# baseboard_0_2.net
KiCad netlist of a schematic drawn in EAGLE
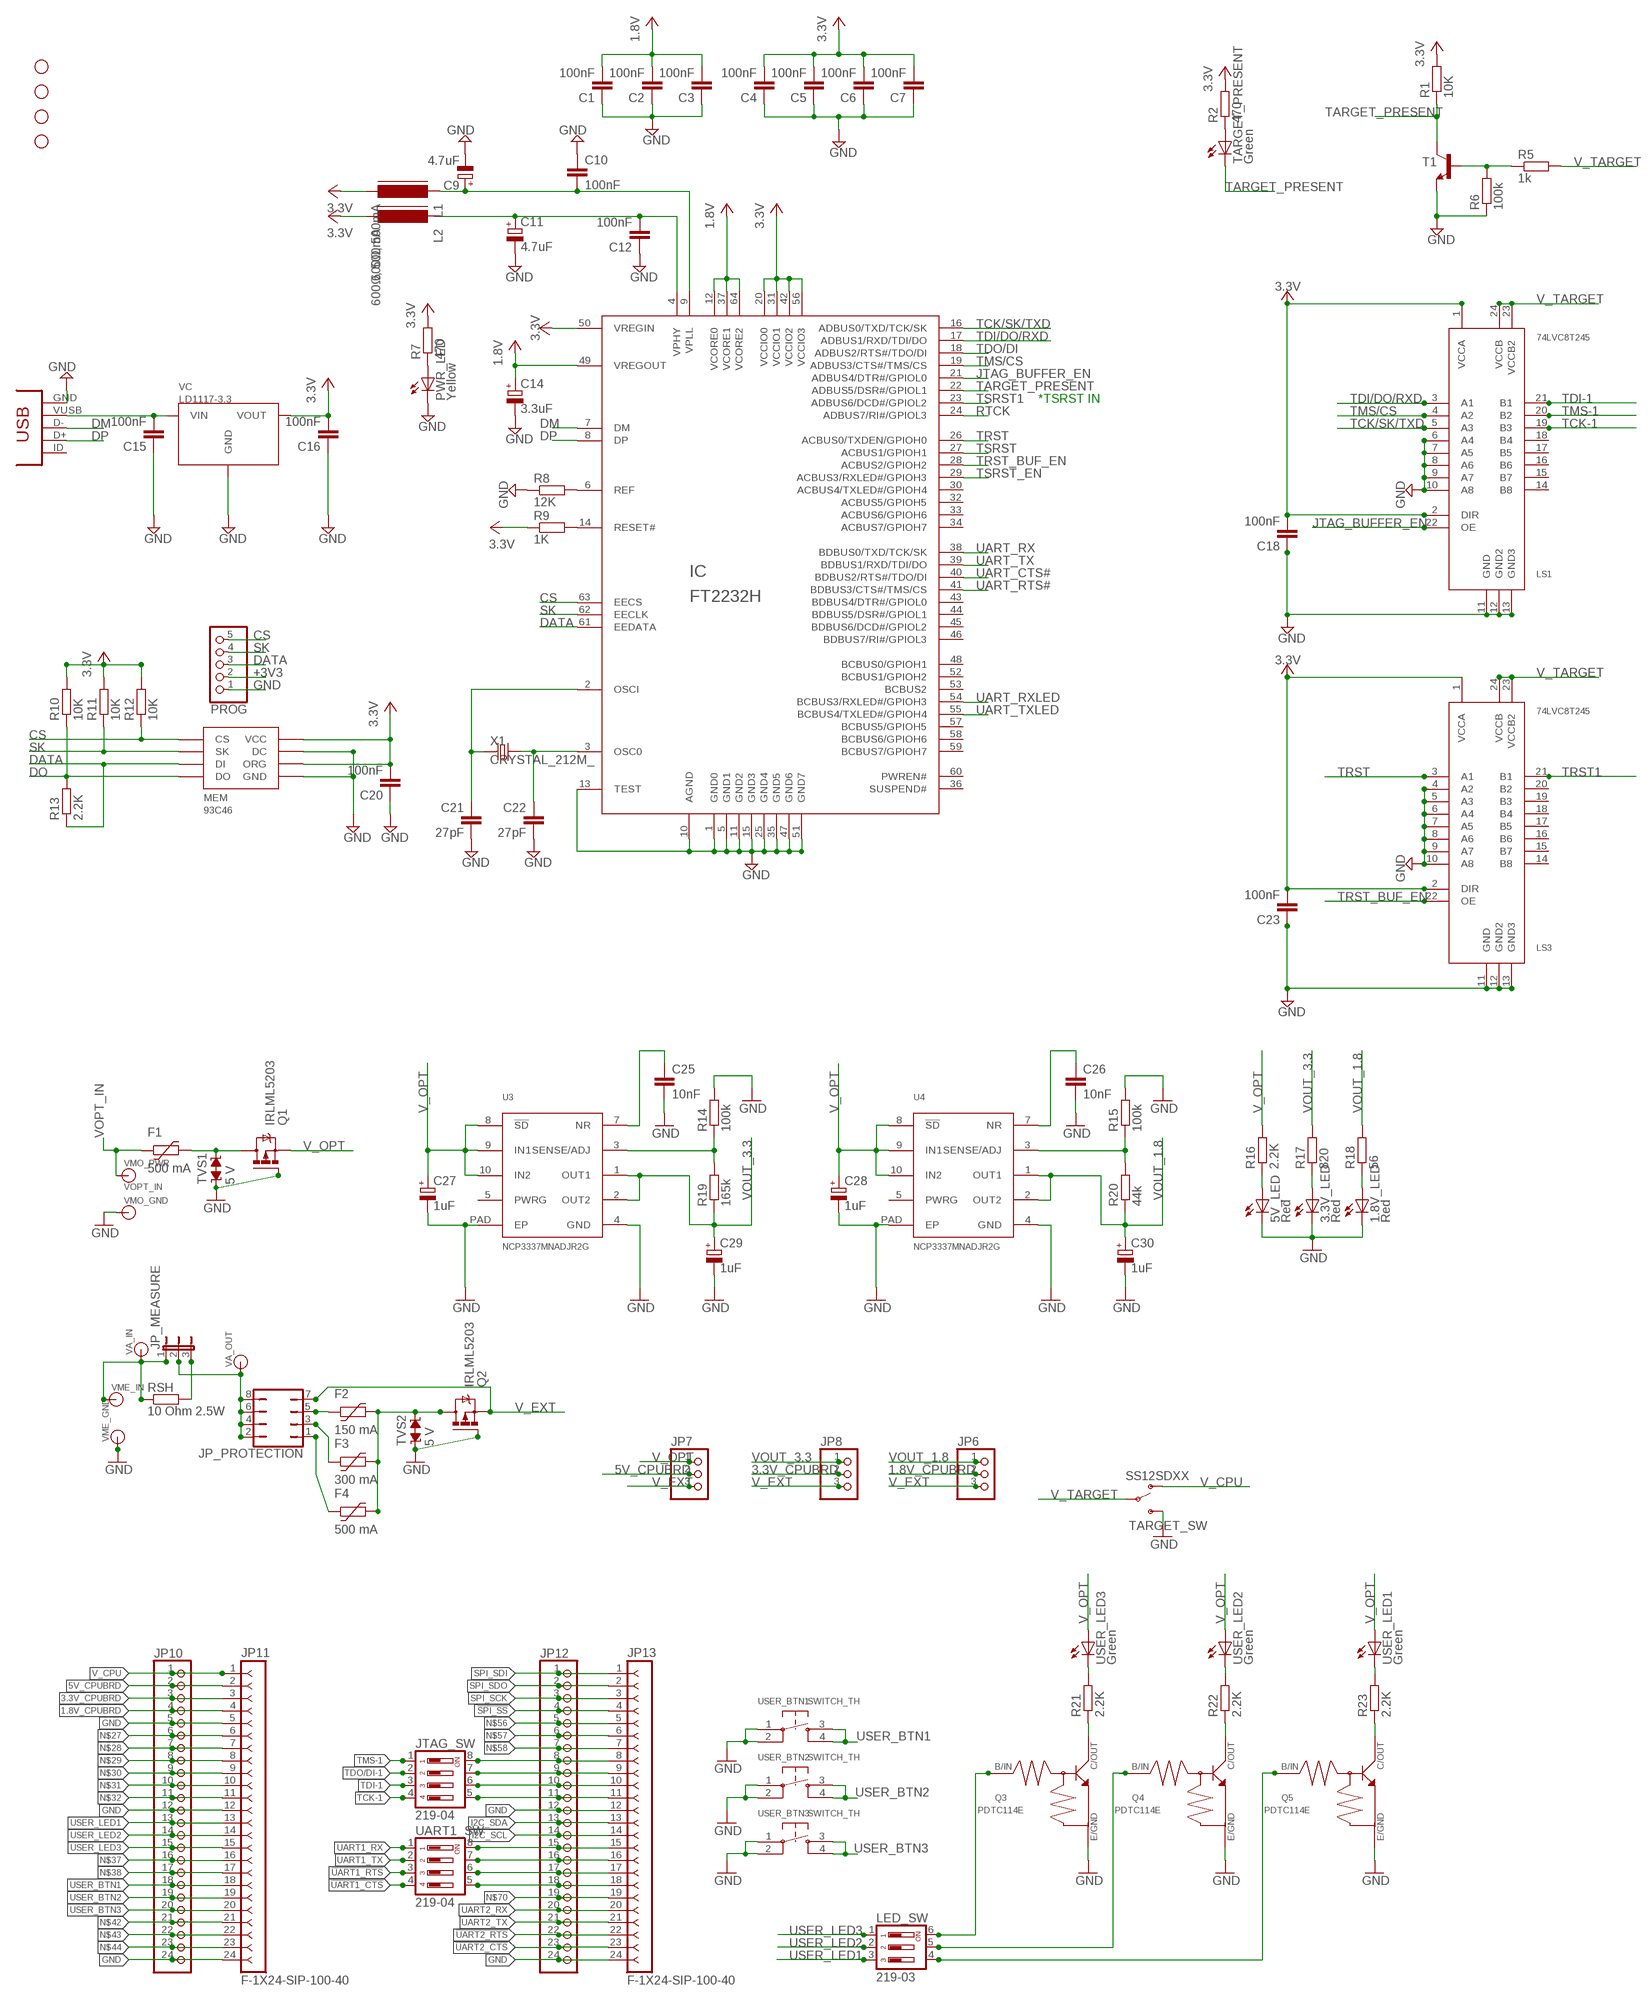
[diagram p0: schematic, sheet 1, part 1 of 2]
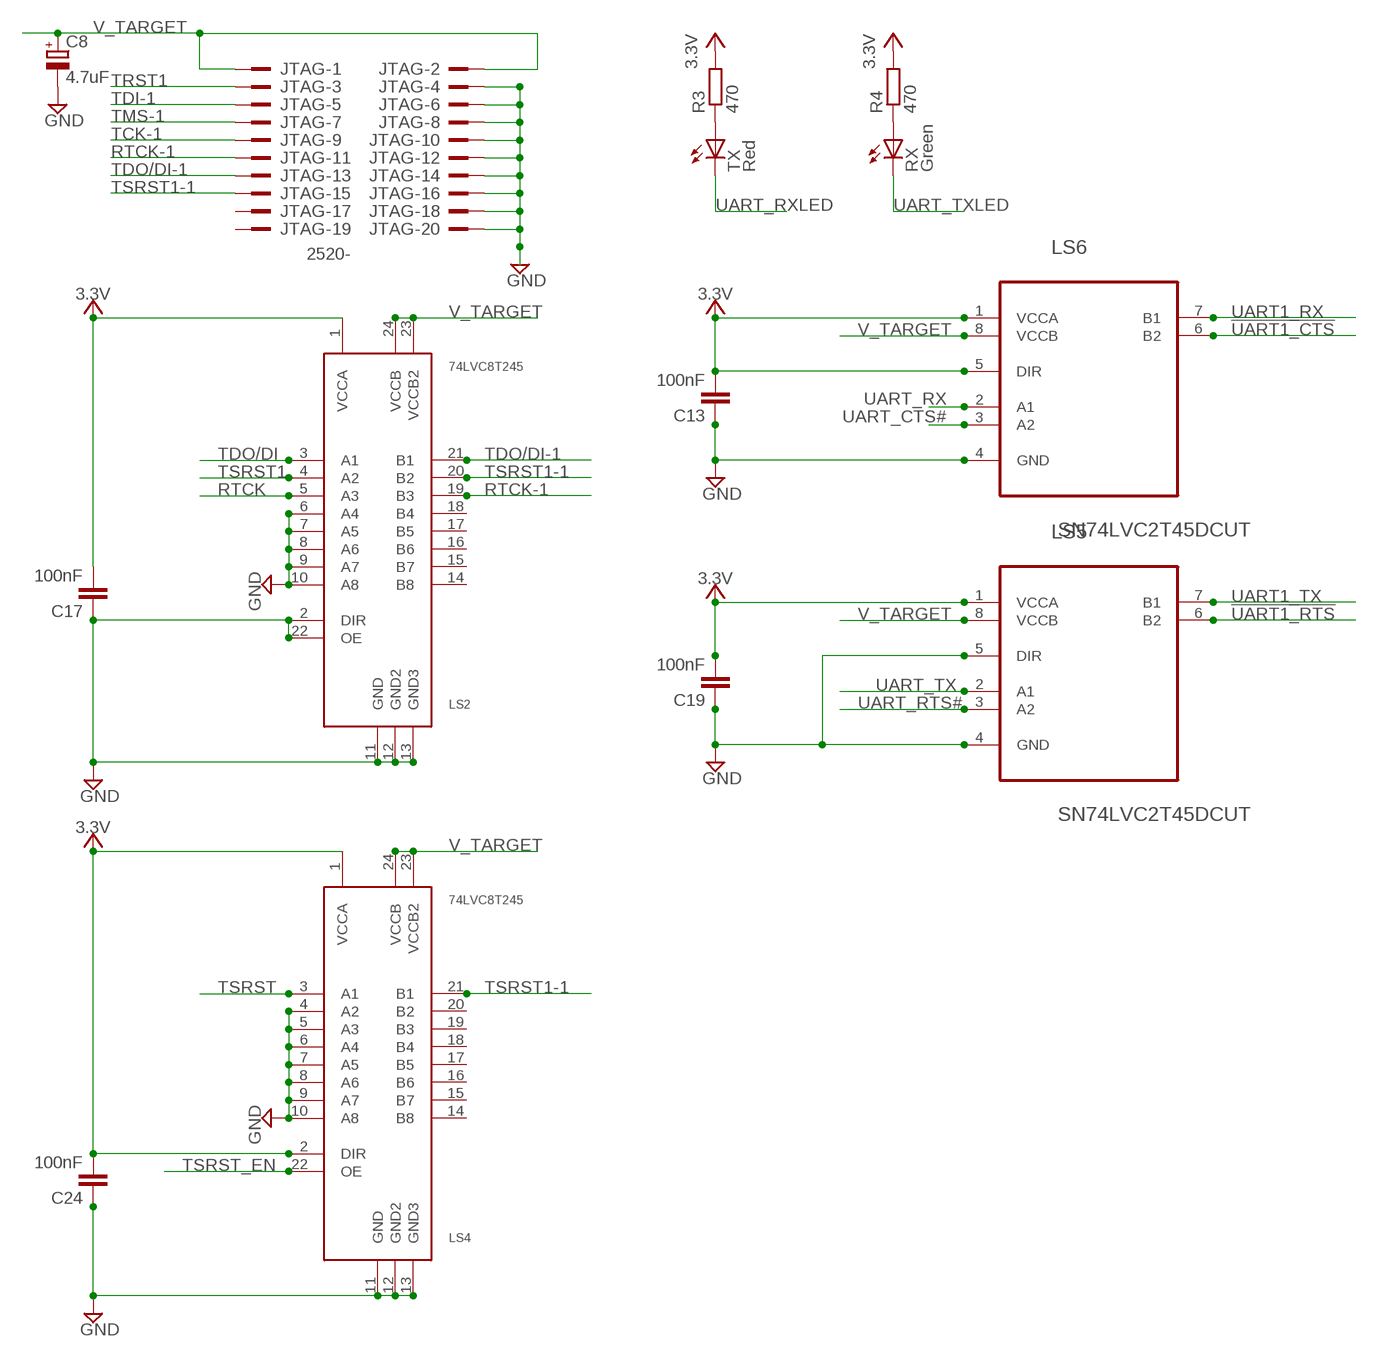
[diagram p1: schematic, sheet 1, part 2 of 2]

(export (version "E")
  (design (tool "Eeschema 10.0.6"))
  (components
    (comp (ref "1.8V_LED")
      (value "Red")
      (footprint "eagle-import:CHIPLED_0805")
      (libsource (lib "eagle-import") (part "LEDCHIPLED_0805"))
    )
    (comp (ref "3.3V_LED")
      (value "Red")
      (footprint "eagle-import:CHIPLED_0805")
      (libsource (lib "eagle-import") (part "LEDCHIPLED_0805"))
    )
    (comp (ref "5V_LED")
      (value "Red")
      (footprint "eagle-import:CHIPLED_0805")
      (libsource (lib "eagle-import") (part "LEDCHIPLED_0805"))
    )
    (comp (ref "C1")
      (value "100nF")
      (footprint "eagle-import:C805")
      (libsource (lib "eagle-import") (part "CAPC805"))
    )
    (comp (ref "C2")
      (value "100nF")
      (footprint "eagle-import:C805")
      (libsource (lib "eagle-import") (part "CAPC805"))
    )
    (comp (ref "C3")
      (value "100nF")
      (footprint "eagle-import:C805")
      (libsource (lib "eagle-import") (part "CAPC805"))
    )
    (comp (ref "C4")
      (value "100nF")
      (footprint "eagle-import:C805")
      (libsource (lib "eagle-import") (part "CAPC805"))
    )
    (comp (ref "C5")
      (value "100nF")
      (footprint "eagle-import:C805")
      (libsource (lib "eagle-import") (part "CAPC805"))
    )
    (comp (ref "C6")
      (value "100nF")
      (footprint "eagle-import:C805")
      (libsource (lib "eagle-import") (part "CAPC805"))
    )
    (comp (ref "C7")
      (value "100nF")
      (footprint "eagle-import:C805")
      (libsource (lib "eagle-import") (part "CAPC805"))
    )
    (comp (ref "C8")
      (value "4.7uF")
      (footprint "eagle-import:SMC_A")
      (libsource (lib "eagle-import") (part "CAP_POLSMC_A"))
    )
    (comp (ref "C9")
      (value "4.7uF")
      (footprint "eagle-import:SMC_A")
      (libsource (lib "eagle-import") (part "CAP_POLSMC_A"))
    )
    (comp (ref "C10")
      (value "100nF")
      (footprint "eagle-import:C805")
      (libsource (lib "eagle-import") (part "CAPC805"))
    )
    (comp (ref "C11")
      (value "4.7uF")
      (footprint "eagle-import:SMC_A")
      (libsource (lib "eagle-import") (part "CAP_POLSMC_A"))
    )
    (comp (ref "C12")
      (value "100nF")
      (footprint "eagle-import:C805")
      (libsource (lib "eagle-import") (part "CAPC805"))
    )
    (comp (ref "C13")
      (value "100nF")
      (footprint "eagle-import:C805")
      (libsource (lib "eagle-import") (part "CAPC805"))
    )
    (comp (ref "C14")
      (value "3.3uF")
      (footprint "eagle-import:SMC_A")
      (libsource (lib "eagle-import") (part "CAP_POLSMC_A"))
    )
    (comp (ref "C15")
      (value "100nF")
      (footprint "eagle-import:C805")
      (libsource (lib "eagle-import") (part "CAPC805"))
    )
    (comp (ref "C16")
      (value "100nF")
      (footprint "eagle-import:C805")
      (libsource (lib "eagle-import") (part "CAPC805"))
    )
    (comp (ref "C17")
      (value "100nF")
      (footprint "eagle-import:C805")
      (libsource (lib "eagle-import") (part "CAPC805"))
    )
    (comp (ref "C18")
      (value "100nF")
      (footprint "eagle-import:C805")
      (libsource (lib "eagle-import") (part "CAPC805"))
    )
    (comp (ref "C19")
      (value "100nF")
      (footprint "eagle-import:C805")
      (libsource (lib "eagle-import") (part "CAPC805"))
    )
    (comp (ref "C20")
      (value "100nF")
      (footprint "eagle-import:C805")
      (libsource (lib "eagle-import") (part "CAPC805"))
    )
    (comp (ref "C21")
      (value "27pF")
      (footprint "eagle-import:C805")
      (libsource (lib "eagle-import") (part "CAPC805"))
    )
    (comp (ref "C22")
      (value "27pF")
      (footprint "eagle-import:C805")
      (libsource (lib "eagle-import") (part "CAPC805"))
    )
    (comp (ref "C23")
      (value "100nF")
      (footprint "eagle-import:C805")
      (libsource (lib "eagle-import") (part "CAPC805"))
    )
    (comp (ref "C24")
      (value "100nF")
      (footprint "eagle-import:C805")
      (libsource (lib "eagle-import") (part "CAPC805"))
    )
    (comp (ref "C25")
      (value "10nF")
      (footprint "eagle-import:C0805")
      (libsource (lib "eagle-import") (part "C-EUC0805"))
    )
    (comp (ref "C26")
      (value "10nF")
      (footprint "eagle-import:C0805")
      (libsource (lib "eagle-import") (part "C-EUC0805"))
    )
    (comp (ref "C27")
      (value "1uF")
      (footprint "eagle-import:PANASONIC_B")
      (libsource (lib "eagle-import") (part "CPOL-EUB"))
    )
    (comp (ref "C28")
      (value "1uF")
      (footprint "eagle-import:PANASONIC_B")
      (libsource (lib "eagle-import") (part "CPOL-EUB"))
    )
    (comp (ref "C29")
      (value "1uF")
      (footprint "eagle-import:PANASONIC_B")
      (libsource (lib "eagle-import") (part "CPOL-EUB"))
    )
    (comp (ref "C30")
      (value "1uF")
      (footprint "eagle-import:PANASONIC_B")
      (libsource (lib "eagle-import") (part "CPOL-EUB"))
    )
    (comp (ref "CONN1")
      (value "CONN_USB")
      (footprint "eagle-import:CONN_USB_MINI-B")
      (libsource (lib "eagle-import") (part "CONN_USB"))
    )
    (comp (ref "F1")
      (value "500 mA")
      (footprint "eagle-import:1206L")
      (libsource (lib "eagle-import") (part "1206L"))
    )
    (comp (ref "F2")
      (value "150 mA")
      (footprint "eagle-import:1206L")
      (libsource (lib "eagle-import") (part "1206L"))
    )
    (comp (ref "F3")
      (value "300 mA")
      (footprint "eagle-import:1206L")
      (libsource (lib "eagle-import") (part "1206L"))
    )
    (comp (ref "F4")
      (value "500 mA")
      (footprint "eagle-import:1206L")
      (libsource (lib "eagle-import") (part "1206L"))
    )
    (comp (ref "IC")
      (value "FT2232H")
      (footprint "eagle-import:LQFP64")
      (libsource (lib "eagle-import") (part "FT2232H"))
    )
    (comp (ref "JP1")
      (value "STAND-OFF")
      (footprint "eagle-import:STAND-OFF")
      (libsource (lib "eagle-import") (part "STAND-OFF"))
    )
    (comp (ref "JP2")
      (value "STAND-OFF")
      (footprint "eagle-import:STAND-OFF")
      (libsource (lib "eagle-import") (part "STAND-OFF"))
    )
    (comp (ref "JP3")
      (value "STAND-OFF")
      (footprint "eagle-import:STAND-OFF")
      (libsource (lib "eagle-import") (part "STAND-OFF"))
    )
    (comp (ref "JP4")
      (value "STAND-OFF")
      (footprint "eagle-import:STAND-OFF")
      (libsource (lib "eagle-import") (part "STAND-OFF"))
    )
    (comp (ref "JP6")
      (value "PINHD-1X3")
      (footprint "eagle-import:1X03")
      (libsource (lib "eagle-import") (part "PINHD-1X3"))
    )
    (comp (ref "JP7")
      (value "PINHD-1X3")
      (footprint "eagle-import:1X03")
      (libsource (lib "eagle-import") (part "PINHD-1X3"))
    )
    (comp (ref "JP8")
      (value "PINHD-1X3")
      (footprint "eagle-import:1X03")
      (libsource (lib "eagle-import") (part "PINHD-1X3"))
    )
    (comp (ref "JP10")
      (value "PINHD-1X24")
      (footprint "eagle-import:1X24")
      (libsource (lib "eagle-import") (part "PINHD-1X24"))
    )
    (comp (ref "JP11")
      (value "F-1X24-SIP-100-40")
      (footprint "eagle-import:SIP-100-24-40")
      (libsource (lib "eagle-import") (part "F-1X24-SIP-100-40"))
    )
    (comp (ref "JP12")
      (value "PINHD-1X24")
      (footprint "eagle-import:1X24")
      (libsource (lib "eagle-import") (part "PINHD-1X24"))
    )
    (comp (ref "JP13")
      (value "F-1X24-SIP-100-40")
      (footprint "eagle-import:SIP-100-24-40")
      (libsource (lib "eagle-import") (part "F-1X24-SIP-100-40"))
    )
    (comp (ref "JP_MEASURE")
      (value "JP2E")
      (footprint "eagle-import:JP2")
      (libsource (lib "eagle-import") (part "JP2E"))
    )
    (comp (ref "JP_PROTECTION")
      (value "JP4Q")
      (footprint "eagle-import:JP4Q")
      (libsource (lib "eagle-import") (part "JP4Q"))
    )
    (comp (ref "JTAG")
      (value "2520-")
      (footprint "eagle-import:PAK100_2500-20")
      (libsource (lib "eagle-import") (part "2520-"))
    )
    (comp (ref "JTAG_SW")
      (value "219-04")
      (footprint "eagle-import:CTS-219-04")
      (libsource (lib "eagle-import") (part "219-04"))
    )
    (comp (ref "L1")
      (value "600Ω, 500mA")
      (footprint "eagle-import:FB805")
      (libsource (lib "eagle-import") (part "FERRITE_BEAD805"))
    )
    (comp (ref "L2")
      (value "600Ω, 500mA")
      (footprint "eagle-import:FB805")
      (libsource (lib "eagle-import") (part "FERRITE_BEAD805"))
    )
    (comp (ref "LED_SW")
      (value "219-03")
      (footprint "eagle-import:CTS-219-03")
      (libsource (lib "eagle-import") (part "219-03"))
    )
    (comp (ref "LS1")
      (value "74LVC8T245")
      (footprint "eagle-import:TSSOP24")
      (libsource (lib "eagle-import") (part "74LVC8T245"))
    )
    (comp (ref "LS2")
      (value "74LVC8T245")
      (footprint "eagle-import:TSSOP24")
      (libsource (lib "eagle-import") (part "74LVC8T245"))
    )
    (comp (ref "LS3")
      (value "74LVC8T245")
      (footprint "eagle-import:TSSOP24")
      (libsource (lib "eagle-import") (part "74LVC8T245"))
    )
    (comp (ref "LS4")
      (value "74LVC8T245")
      (footprint "eagle-import:TSSOP24")
      (libsource (lib "eagle-import") (part "74LVC8T245"))
    )
    (comp (ref "LS5")
      (value "SN74LVC2T45DCUT")
      (footprint "eagle-import:SOP50P310X90-8N")
      (libsource (lib "eagle-import") (part "SN74LVC2T45DCUT"))
    )
    (comp (ref "LS6")
      (value "SN74LVC2T45DCUT")
      (footprint "eagle-import:SOP50P310X90-8N")
      (libsource (lib "eagle-import") (part "SN74LVC2T45DCUT"))
    )
    (comp (ref "MEM")
      (value "93C46")
      (footprint "eagle-import:SOIC8")
      (libsource (lib "eagle-import") (part "93C46"))
    )
    (comp (ref "PROG")
      (value "PINHD-1X5")
      (footprint "eagle-import:1X05")
      (libsource (lib "eagle-import") (part "PINHD-1X5"))
    )
    (comp (ref "PWR_LED")
      (value "Yellow")
      (footprint "eagle-import:CHIPLED_0805")
      (libsource (lib "eagle-import") (part "led_LEDCHIPLED_0805"))
    )
    (comp (ref "Q1")
      (value "IRLML5203")
      (footprint "eagle-import:MICRO3")
      (libsource (lib "eagle-import") (part "IRLML5203"))
    )
    (comp (ref "Q2")
      (value "IRLML5203")
      (footprint "eagle-import:MICRO3")
      (libsource (lib "eagle-import") (part "IRLML5203"))
    )
    (comp (ref "Q3")
      (value "PDTC114E")
      (footprint "eagle-import:SOT416")
      (libsource (lib "eagle-import") (part "PDTC114E"))
    )
    (comp (ref "Q4")
      (value "PDTC114E")
      (footprint "eagle-import:SOT416")
      (libsource (lib "eagle-import") (part "PDTC114E"))
    )
    (comp (ref "Q5")
      (value "PDTC114E")
      (footprint "eagle-import:SOT416")
      (libsource (lib "eagle-import") (part "PDTC114E"))
    )
    (comp (ref "R1")
      (value "10K")
      (footprint "eagle-import:R805")
      (libsource (lib "eagle-import") (part "RESISTORR805R805"))
    )
    (comp (ref "R2")
      (value "470")
      (footprint "eagle-import:R805")
      (libsource (lib "eagle-import") (part "RESISTORR805R805"))
    )
    (comp (ref "R3")
      (value "470")
      (footprint "eagle-import:R805")
      (libsource (lib "eagle-import") (part "RESISTORR805R805"))
    )
    (comp (ref "R4")
      (value "470")
      (footprint "eagle-import:R805")
      (libsource (lib "eagle-import") (part "RESISTORR805R805"))
    )
    (comp (ref "R5")
      (value "1k")
      (footprint "eagle-import:R805")
      (libsource (lib "eagle-import") (part "RESISTORR805R805"))
    )
    (comp (ref "R6")
      (value "100k")
      (footprint "eagle-import:R805")
      (libsource (lib "eagle-import") (part "RESISTORR805R805"))
    )
    (comp (ref "R7")
      (value "470")
      (footprint "eagle-import:R805")
      (libsource (lib "eagle-import") (part "RESISTORR805R805"))
    )
    (comp (ref "R8")
      (value "12K")
      (footprint "eagle-import:R805")
      (libsource (lib "eagle-import") (part "RESISTORR805R805"))
    )
    (comp (ref "R9")
      (value "1K")
      (footprint "eagle-import:R805")
      (libsource (lib "eagle-import") (part "RESISTORR805R805"))
    )
    (comp (ref "R10")
      (value "10K")
      (footprint "eagle-import:R805")
      (libsource (lib "eagle-import") (part "RESISTORR805R805"))
    )
    (comp (ref "R11")
      (value "10K")
      (footprint "eagle-import:R805")
      (libsource (lib "eagle-import") (part "RESISTORR805R805"))
    )
    (comp (ref "R12")
      (value "10K")
      (footprint "eagle-import:R805")
      (libsource (lib "eagle-import") (part "RESISTORR805R805"))
    )
    (comp (ref "R13")
      (value "2.2K")
      (footprint "eagle-import:R805")
      (libsource (lib "eagle-import") (part "RESISTORR805R805"))
    )
    (comp (ref "R14")
      (value "100k")
      (footprint "eagle-import:R0805")
      (libsource (lib "eagle-import") (part "R-EU_R0805"))
    )
    (comp (ref "R15")
      (value "100k")
      (footprint "eagle-import:R0805")
      (libsource (lib "eagle-import") (part "R-EU_R0805"))
    )
    (comp (ref "R16")
      (value "2.2K")
      (footprint "eagle-import:R0805")
      (libsource (lib "eagle-import") (part "R-EU_R0805"))
    )
    (comp (ref "R17")
      (value "820")
      (footprint "eagle-import:R0805")
      (libsource (lib "eagle-import") (part "R-EU_R0805"))
    )
    (comp (ref "R18")
      (value "56")
      (footprint "eagle-import:R0805")
      (libsource (lib "eagle-import") (part "R-EU_R0805"))
    )
    (comp (ref "R19")
      (value "165k")
      (footprint "eagle-import:R0805")
      (libsource (lib "eagle-import") (part "R-EU_R0805"))
    )
    (comp (ref "R20")
      (value "44k")
      (footprint "eagle-import:R0805")
      (libsource (lib "eagle-import") (part "R-EU_R0805"))
    )
    (comp (ref "R21")
      (value "2.2K")
      (footprint "eagle-import:R0805")
      (libsource (lib "eagle-import") (part "R-EU_R0805"))
    )
    (comp (ref "R22")
      (value "2.2K")
      (footprint "eagle-import:R0805")
      (libsource (lib "eagle-import") (part "R-EU_R0805"))
    )
    (comp (ref "R23")
      (value "2.2K")
      (footprint "eagle-import:R0805")
      (libsource (lib "eagle-import") (part "R-EU_R0805"))
    )
    (comp (ref "RSH")
      (value "10 Ohm 2.5W")
      (footprint "eagle-import:R2512")
      (libsource (lib "eagle-import") (part "R-EU_R2512"))
    )
    (comp (ref "RX")
      (value "Green")
      (footprint "eagle-import:CHIPLED_0805")
      (libsource (lib "eagle-import") (part "led_LEDCHIPLED_0805"))
    )
    (comp (ref "T1")
      (value "NPNSOT23BEC")
      (footprint "eagle-import:SOT23-BEC")
      (libsource (lib "eagle-import") (part "NPNSOT23BEC"))
    )
    (comp (ref "TARGET_PRESENT")
      (value "Green")
      (footprint "eagle-import:CHIPLED_0805")
      (libsource (lib "eagle-import") (part "led_LEDCHIPLED_0805"))
    )
    (comp (ref "TARGET_SW")
      (value "SS12SDXX")
      (footprint "eagle-import:SS12SDXX")
      (libsource (lib "eagle-import") (part "SS12SDXX"))
    )
    (comp (ref "TVS1")
      (value "5 V")
      (footprint "eagle-import:TVS0805")
      (libsource (lib "eagle-import") (part "TVS-0805"))
    )
    (comp (ref "TVS2")
      (value "5 V")
      (footprint "eagle-import:TVS0805")
      (libsource (lib "eagle-import") (part "TVS-0805"))
    )
    (comp (ref "TX")
      (value "Red")
      (footprint "eagle-import:CHIPLED_0805")
      (libsource (lib "eagle-import") (part "led_LEDCHIPLED_0805"))
    )
    (comp (ref "U3")
      (value "NCP3337MNADJR2G")
      (footprint "eagle-import:DFN10")
      (libsource (lib "eagle-import") (part "NCP3337"))
    )
    (comp (ref "U4")
      (value "NCP3337MNADJR2G")
      (footprint "eagle-import:DFN10")
      (libsource (lib "eagle-import") (part "NCP3337"))
    )
    (comp (ref "UART1_SW")
      (value "219-04")
      (footprint "eagle-import:CTS-219-04")
      (libsource (lib "eagle-import") (part "219-04"))
    )
    (comp (ref "USER_BTN1")
      (value "SWITCH_TH")
      (footprint "eagle-import:SWITCH_TROUGHHOLE")
      (libsource (lib "eagle-import") (part "SWITCH_TH"))
    )
    (comp (ref "USER_BTN2")
      (value "SWITCH_TH")
      (footprint "eagle-import:SWITCH_TROUGHHOLE")
      (libsource (lib "eagle-import") (part "SWITCH_TH"))
    )
    (comp (ref "USER_BTN3")
      (value "SWITCH_TH")
      (footprint "eagle-import:SWITCH_TROUGHHOLE")
      (libsource (lib "eagle-import") (part "SWITCH_TH"))
    )
    (comp (ref "USER_LED1")
      (value "Green")
      (footprint "eagle-import:CHIPLED_0805")
      (libsource (lib "eagle-import") (part "LEDCHIPLED_0805"))
    )
    (comp (ref "USER_LED2")
      (value "Green")
      (footprint "eagle-import:CHIPLED_0805")
      (libsource (lib "eagle-import") (part "LEDCHIPLED_0805"))
    )
    (comp (ref "USER_LED3")
      (value "Green")
      (footprint "eagle-import:CHIPLED_0805")
      (libsource (lib "eagle-import") (part "LEDCHIPLED_0805"))
    )
    (comp (ref "VA_IN")
      (value "BANANA_CONN")
      (footprint "eagle-import:BANANA_CONN")
      (libsource (lib "eagle-import") (part "BANANA_CONN"))
    )
    (comp (ref "VA_OUT")
      (value "BANANA_CONN")
      (footprint "eagle-import:BANANA_CONN")
      (libsource (lib "eagle-import") (part "BANANA_CONN"))
    )
    (comp (ref "VC")
      (value "LD1117-3.3")
      (footprint "eagle-import:SOT223")
      (libsource (lib "eagle-import") (part "LD1117-3.3"))
    )
    (comp (ref "VME_GND")
      (value "BANANA_CONN")
      (footprint "eagle-import:BANANA_CONN")
      (libsource (lib "eagle-import") (part "BANANA_CONN"))
    )
    (comp (ref "VME_IN")
      (value "BANANA_CONN")
      (footprint "eagle-import:BANANA_CONN")
      (libsource (lib "eagle-import") (part "BANANA_CONN"))
    )
    (comp (ref "VMO_GND")
      (value "BANANA_CONN")
      (footprint "eagle-import:BANANA_CONN")
      (libsource (lib "eagle-import") (part "BANANA_CONN"))
    )
    (comp (ref "VMO_PWR")
      (value "VOPT_IN")
      (footprint "eagle-import:BANANA_CONN")
      (libsource (lib "eagle-import") (part "BANANA_CONN"))
    )
    (comp (ref "X1")
      (value "CRYSTAL_212M_")
      (footprint "eagle-import:4X6")
      (libsource (lib "eagle-import") (part "CRYSTAL_212M_"))
    )
  )
  (nets
    (net (code "1") (name "/CS") (class "Default")
      (node (ref "IC") (pin "63") (pinfunction "EECS_63") (pintype "bidirectional"))
      (node (ref "MEM") (pin "1") (pinfunction "CS_1") (pintype "bidirectional"))
      (node (ref "PROG") (pin "5") (pinfunction "5_5") (pintype "passive"))
      (node (ref "R12") (pin "1") (pinfunction "1_1") (pintype "passive"))
    )
    (net (code "2") (name "/DATA") (class "Default")
      (node (ref "IC") (pin "61") (pinfunction "EEDATA_61") (pintype "bidirectional"))
      (node (ref "MEM") (pin "3") (pinfunction "DI_3") (pintype "bidirectional"))
      (node (ref "PROG") (pin "3") (pinfunction "3_3") (pintype "passive"))
      (node (ref "R13") (pin "1") (pinfunction "1_1") (pintype "passive"))
    )
    (net (code "3") (name "/DM") (class "Default")
      (node (ref "CONN1") (pin "D-") (pinfunction "D-_D-") (pintype "bidirectional"))
      (node (ref "IC") (pin "7") (pinfunction "DM_7") (pintype "bidirectional"))
    )
    (net (code "4") (name "/DO") (class "Default")
      (node (ref "MEM") (pin "4") (pinfunction "DO_4") (pintype "bidirectional"))
      (node (ref "R10") (pin "1") (pinfunction "1_1") (pintype "passive"))
      (node (ref "R13") (pin "2") (pinfunction "2_2") (pintype "passive"))
    )
    (net (code "5") (name "/DP") (class "Default")
      (node (ref "CONN1") (pin "D+") (pinfunction "D+_D+") (pintype "bidirectional"))
      (node (ref "IC") (pin "8") (pinfunction "DP_8") (pintype "bidirectional"))
    )
    (net (code "6") (name "/JTAG_BUFFER_EN") (class "Default")
      (node (ref "IC") (pin "21") (pinfunction "ADBUS4/DTR#/GPIOL0_21") (pintype "bidirectional"))
      (node (ref "LS1") (pin "22") (pinfunction "OE_22") (pintype "bidirectional"))
    )
    (net (code "7") (name "/RTCK") (class "Default")
      (node (ref "IC") (pin "24") (pinfunction "ADBUS7/RI#/GPIOL3_24") (pintype "bidirectional"))
      (node (ref "LS2") (pin "5") (pinfunction "A3_5") (pintype "bidirectional"))
    )
    (net (code "8") (name "/RTCK-1") (class "Default")
      (node (ref "JTAG") (pin "11") (pinfunction "KL_11") (pintype "passive"))
      (node (ref "LS2") (pin "19") (pinfunction "B3_19") (pintype "bidirectional"))
    )
    (net (code "9") (name "/SK") (class "Default")
      (node (ref "IC") (pin "62") (pinfunction "EECLK_62") (pintype "bidirectional"))
      (node (ref "MEM") (pin "2") (pinfunction "SK_2") (pintype "bidirectional"))
      (node (ref "PROG") (pin "4") (pinfunction "4_4") (pintype "passive"))
      (node (ref "R11") (pin "1") (pinfunction "1_1") (pintype "passive"))
    )
    (net (code "10") (name "/TARGET_PRESENT") (class "Default")
      (node (ref "IC") (pin "22") (pinfunction "ADBUS5/DSR#/GPIOL1_22") (pintype "bidirectional"))
      (node (ref "R1") (pin "1") (pinfunction "1_1") (pintype "passive"))
      (node (ref "T1") (pin "C") (pinfunction "C_C") (pintype "passive"))
      (node (ref "TARGET_PRESENT") (pin "C") (pinfunction "C_C") (pintype "passive"))
    )
    (net (code "11") (name "/TCK{slash}SK{slash}TXD") (class "Default")
      (node (ref "IC") (pin "16") (pinfunction "ADBUS0/TXD/TCK/SK_16") (pintype "bidirectional"))
      (node (ref "LS1") (pin "5") (pinfunction "A3_5") (pintype "bidirectional"))
    )
    (net (code "12") (name "/TDI{slash}DO{slash}RXD") (class "Default")
      (node (ref "IC") (pin "17") (pinfunction "ADBUS1/RXD/TDI/DO_17") (pintype "bidirectional"))
      (node (ref "LS1") (pin "3") (pinfunction "A1_3") (pintype "bidirectional"))
    )
    (net (code "13") (name "/TDO{slash}DI") (class "Default")
      (node (ref "IC") (pin "18") (pinfunction "ADBUS2/RTS#/TDO/DI_18") (pintype "bidirectional"))
      (node (ref "LS2") (pin "3") (pinfunction "A1_3") (pintype "bidirectional"))
    )
    (net (code "14") (name "/TMS{slash}CS") (class "Default")
      (node (ref "IC") (pin "19") (pinfunction "ADBUS3/CTS#/TMS/CS_19") (pintype "bidirectional"))
      (node (ref "LS1") (pin "4") (pinfunction "A2_4") (pintype "bidirectional"))
    )
    (net (code "15") (name "/TRST") (class "Default")
      (node (ref "IC") (pin "26") (pinfunction "ACBUS0/TXDEN/GPIOH0_26") (pintype "bidirectional"))
      (node (ref "LS3") (pin "3") (pinfunction "A1_3") (pintype "bidirectional"))
    )
    (net (code "16") (name "/TRST1") (class "Default")
      (node (ref "JTAG") (pin "3") (pinfunction "KL_3") (pintype "passive"))
      (node (ref "LS3") (pin "21") (pinfunction "B1_21") (pintype "bidirectional"))
    )
    (net (code "17") (name "/TRST_BUF_EN") (class "Default")
      (node (ref "IC") (pin "28") (pinfunction "ACBUS2/GPIOH2_28") (pintype "bidirectional"))
      (node (ref "LS3") (pin "22") (pinfunction "OE_22") (pintype "bidirectional"))
    )
    (net (code "18") (name "/TSRST") (class "Default")
      (node (ref "IC") (pin "27") (pinfunction "ACBUS1/GPIOH1_27") (pintype "bidirectional"))
      (node (ref "LS4") (pin "3") (pinfunction "A1_3") (pintype "bidirectional"))
    )
    (net (code "19") (name "/TSRST1") (class "Default")
      (node (ref "IC") (pin "23") (pinfunction "ADBUS6/DCD#/GPIOL2_23") (pintype "bidirectional"))
      (node (ref "LS2") (pin "4") (pinfunction "A2_4") (pintype "bidirectional"))
    )
    (net (code "20") (name "/TSRST1-1") (class "Default")
      (node (ref "JTAG") (pin "15") (pinfunction "KL_15") (pintype "passive"))
      (node (ref "LS2") (pin "20") (pinfunction "B2_20") (pintype "bidirectional"))
      (node (ref "LS4") (pin "21") (pinfunction "B1_21") (pintype "bidirectional"))
    )
    (net (code "21") (name "/TSRST_EN") (class "Default")
      (node (ref "IC") (pin "29") (pinfunction "ACBUS3/RXLED#/GPIOH3_29") (pintype "bidirectional"))
      (node (ref "LS4") (pin "22") (pinfunction "OE_22") (pintype "bidirectional"))
    )
    (net (code "22") (name "/UART_CTS#") (class "Default")
      (node (ref "IC") (pin "40") (pinfunction "BDBUS2/RTS#/TDO/DI_40") (pintype "bidirectional"))
      (node (ref "LS6") (pin "3") (pinfunction "A2_3") (pintype "bidirectional"))
    )
    (net (code "23") (name "/UART_RTS#") (class "Default")
      (node (ref "IC") (pin "41") (pinfunction "BDBUS3/CTS#/TMS/CS_41") (pintype "bidirectional"))
      (node (ref "LS5") (pin "3") (pinfunction "A2_3") (pintype "bidirectional"))
    )
    (net (code "24") (name "/UART_RX") (class "Default")
      (node (ref "IC") (pin "38") (pinfunction "BDBUS0/TXD/TCK/SK_38") (pintype "bidirectional"))
      (node (ref "LS6") (pin "2") (pinfunction "A1_2") (pintype "bidirectional"))
    )
    (net (code "25") (name "/UART_RXLED") (class "Default")
      (node (ref "IC") (pin "54") (pinfunction "BCBUS3/RXLED#/GPIOH3_54") (pintype "bidirectional"))
      (node (ref "TX") (pin "C") (pinfunction "C_C") (pintype "passive"))
    )
    (net (code "26") (name "/UART_TX") (class "Default")
      (node (ref "IC") (pin "39") (pinfunction "BDBUS1/RXD/TDI/DO_39") (pintype "bidirectional"))
      (node (ref "LS5") (pin "2") (pinfunction "A1_2") (pintype "bidirectional"))
    )
    (net (code "27") (name "/UART_TXLED") (class "Default")
      (node (ref "IC") (pin "55") (pinfunction "BCBUS4/TXLED#/GPIOH4_55") (pintype "bidirectional"))
      (node (ref "RX") (pin "C") (pinfunction "C_C") (pintype "passive"))
    )
    (net (code "28") (name "/VOPT_IN") (class "Default")
      (node (ref "F1") (pin "P$1") (pinfunction "1_P$1") (pintype "passive"))
      (node (ref "VMO_PWR") (pin "P$1") (pinfunction "1_P$1") (pintype "passive"))
    )
    (net (code "29") (name "/VOUT_1.8") (class "Default")
      (node (ref "C30") (pin "+") (pinfunction "+_+") (pintype "passive"))
      (node (ref "JP6") (pin "1") (pinfunction "1_1") (pintype "passive"))
      (node (ref "R18") (pin "2") (pinfunction "2_2") (pintype "passive"))
      (node (ref "R20") (pin "1") (pinfunction "1_1") (pintype "passive"))
      (node (ref "U4") (pin "1") (pinfunction "OUT1_1") (pintype "bidirectional"))
      (node (ref "U4") (pin "2") (pinfunction "OUT2_2") (pintype "bidirectional"))
    )
    (net (code "30") (name "/VOUT_3.3") (class "Default")
      (node (ref "C29") (pin "+") (pinfunction "+_+") (pintype "passive"))
      (node (ref "JP8") (pin "1") (pinfunction "1_1") (pintype "passive"))
      (node (ref "R17") (pin "2") (pinfunction "2_2") (pintype "passive"))
      (node (ref "R19") (pin "1") (pinfunction "1_1") (pintype "passive"))
      (node (ref "U3") (pin "1") (pinfunction "OUT1_1") (pintype "bidirectional"))
      (node (ref "U3") (pin "2") (pinfunction "OUT2_2") (pintype "bidirectional"))
    )
    (net (code "31") (name "/V_EXT") (class "Default")
      (node (ref "JP6") (pin "3") (pinfunction "3_3") (pintype "passive"))
      (node (ref "JP7") (pin "3") (pinfunction "3_3") (pintype "passive"))
      (node (ref "JP8") (pin "3") (pinfunction "3_3") (pintype "passive"))
      (node (ref "JP_PROTECTION") (pin "7") (pinfunction "7_7") (pintype "passive"))
      (node (ref "Q2") (pin "2") (pinfunction "S_2") (pintype "passive"))
    )
    (net (code "32") (name "/V_OPT") (class "Default")
      (node (ref "C27") (pin "+") (pinfunction "+_+") (pintype "passive"))
      (node (ref "C28") (pin "+") (pinfunction "+_+") (pintype "passive"))
      (node (ref "JP7") (pin "1") (pinfunction "1_1") (pintype "passive"))
      (node (ref "Q1") (pin "2") (pinfunction "S_2") (pintype "passive"))
      (node (ref "R16") (pin "2") (pinfunction "2_2") (pintype "passive"))
      (node (ref "U3") (pin "10") (pinfunction "IN2_10") (pintype "bidirectional"))
      (node (ref "U3") (pin "8") (pinfunction "~{SD}_8") (pintype "bidirectional"))
      (node (ref "U3") (pin "9") (pinfunction "IN1_9") (pintype "bidirectional"))
      (node (ref "U4") (pin "10") (pinfunction "IN2_10") (pintype "bidirectional"))
      (node (ref "U4") (pin "8") (pinfunction "~{SD}_8") (pintype "bidirectional"))
      (node (ref "U4") (pin "9") (pinfunction "IN1_9") (pintype "bidirectional"))
      (node (ref "USER_LED1") (pin "A") (pinfunction "A_A") (pintype "passive"))
      (node (ref "USER_LED2") (pin "A") (pinfunction "A_A") (pintype "passive"))
      (node (ref "USER_LED3") (pin "A") (pinfunction "A_A") (pintype "passive"))
    )
    (net (code "33") (name "/V_TARGET") (class "Default")
      (node (ref "C8") (pin "+") (pinfunction "+_+") (pintype "passive"))
      (node (ref "JTAG") (pin "1") (pinfunction "KL_1") (pintype "passive"))
      (node (ref "JTAG") (pin "2") (pinfunction "KL_2") (pintype "passive"))
      (node (ref "LS1") (pin "23") (pinfunction "VCCB2_23") (pintype "bidirectional"))
      (node (ref "LS1") (pin "24") (pinfunction "VCCB_24") (pintype "bidirectional"))
      (node (ref "LS2") (pin "23") (pinfunction "VCCB2_23") (pintype "bidirectional"))
      (node (ref "LS2") (pin "24") (pinfunction "VCCB_24") (pintype "bidirectional"))
      (node (ref "LS3") (pin "23") (pinfunction "VCCB2_23") (pintype "bidirectional"))
      (node (ref "LS3") (pin "24") (pinfunction "VCCB_24") (pintype "bidirectional"))
      (node (ref "LS4") (pin "23") (pinfunction "VCCB2_23") (pintype "bidirectional"))
      (node (ref "LS4") (pin "24") (pinfunction "VCCB_24") (pintype "bidirectional"))
      (node (ref "LS5") (pin "8") (pinfunction "VCCB_8") (pintype "power_in"))
      (node (ref "LS6") (pin "8") (pinfunction "VCCB_8") (pintype "power_in"))
      (node (ref "R5") (pin "2") (pinfunction "2_2") (pintype "passive"))
      (node (ref "TARGET_SW") (pin "2") (pinfunction "2_2") (pintype "passive"))
    )
    (net (code "34") (name "/~{SPI_SS}") (class "Default")
      (node (ref "JP12") (pin "4") (pinfunction "4_4") (pintype "passive"))
      (node (ref "JP13") (pin "4") (pinfunction "4_4") (pintype "passive"))
    )
    (net (code "35") (name "/~{UART1_CTS}") (class "Default")
      (node (ref "LS6") (pin "6") (pinfunction "B2_6") (pintype "bidirectional"))
      (node (ref "UART1_SW") (pin "4") (pinfunction "4_4") (pintype "passive"))
    )
    (net (code "36") (name "/~{UART1_RTS}") (class "Default")
      (node (ref "LS5") (pin "6") (pinfunction "B2_6") (pintype "bidirectional"))
      (node (ref "UART1_SW") (pin "3") (pinfunction "3_3") (pintype "passive"))
    )
    (net (code "37") (name "/~{UART2_CTS}") (class "Default")
      (node (ref "JP12") (pin "23") (pinfunction "23_23") (pintype "passive"))
      (node (ref "JP13") (pin "23") (pinfunction "23_23") (pintype "passive"))
    )
    (net (code "38") (name "/~{UART2_RTS}") (class "Default")
      (node (ref "JP12") (pin "22") (pinfunction "22_22") (pintype "passive"))
      (node (ref "JP13") (pin "22") (pinfunction "22_22") (pintype "passive"))
    )
    (net (code "39") (name "1.8V") (class "Default")
      (node (ref "C1") (pin "2") (pinfunction "2_2") (pintype "passive"))
      (node (ref "C14") (pin "+") (pinfunction "+_+") (pintype "passive"))
      (node (ref "C2") (pin "2") (pinfunction "2_2") (pintype "passive"))
      (node (ref "C3") (pin "2") (pinfunction "2_2") (pintype "passive"))
      (node (ref "IC") (pin "12") (pinfunction "VCORE0_12") (pintype "bidirectional"))
      (node (ref "IC") (pin "37") (pinfunction "VCORE1_37") (pintype "bidirectional"))
      (node (ref "IC") (pin "49") (pinfunction "VREGOUT_49") (pintype "bidirectional"))
      (node (ref "IC") (pin "64") (pinfunction "VCORE2_64") (pintype "bidirectional"))
    )
    (net (code "40") (name "1.8V_CPUBRD") (class "Default")
      (node (ref "JP10") (pin "4") (pinfunction "4_4") (pintype "passive"))
      (node (ref "JP11") (pin "4") (pinfunction "4_4") (pintype "passive"))
      (node (ref "JP6") (pin "2") (pinfunction "2_2") (pintype "passive"))
    )
    (net (code "41") (name "3.3V") (class "Default")
      (node (ref "C13") (pin "2") (pinfunction "2_2") (pintype "passive"))
      (node (ref "C16") (pin "2") (pinfunction "2_2") (pintype "passive"))
      (node (ref "C17") (pin "2") (pinfunction "2_2") (pintype "passive"))
      (node (ref "C18") (pin "2") (pinfunction "2_2") (pintype "passive"))
      (node (ref "C19") (pin "2") (pinfunction "2_2") (pintype "passive"))
      (node (ref "C20") (pin "2") (pinfunction "2_2") (pintype "passive"))
      (node (ref "C23") (pin "2") (pinfunction "2_2") (pintype "passive"))
      (node (ref "C24") (pin "2") (pinfunction "2_2") (pintype "passive"))
      (node (ref "C4") (pin "2") (pinfunction "2_2") (pintype "passive"))
      (node (ref "C5") (pin "2") (pinfunction "2_2") (pintype "passive"))
      (node (ref "C6") (pin "2") (pinfunction "2_2") (pintype "passive"))
      (node (ref "C7") (pin "2") (pinfunction "2_2") (pintype "passive"))
      (node (ref "IC") (pin "20") (pinfunction "VCCIO0_20") (pintype "bidirectional"))
      (node (ref "IC") (pin "31") (pinfunction "VCCIO1_31") (pintype "bidirectional"))
      (node (ref "IC") (pin "42") (pinfunction "VCCIO2_42") (pintype "bidirectional"))
      (node (ref "IC") (pin "50") (pinfunction "VREGIN_50") (pintype "bidirectional"))
      (node (ref "IC") (pin "56") (pinfunction "VCCIO3_56") (pintype "bidirectional"))
      (node (ref "L1") (pin "2") (pinfunction "2_2") (pintype "passive"))
      (node (ref "L2") (pin "2") (pinfunction "2_2") (pintype "passive"))
      (node (ref "LS1") (pin "1") (pinfunction "VCCA_1") (pintype "bidirectional"))
      (node (ref "LS1") (pin "2") (pinfunction "DIR_2") (pintype "bidirectional"))
      (node (ref "LS2") (pin "1") (pinfunction "VCCA_1") (pintype "bidirectional"))
      (node (ref "LS3") (pin "1") (pinfunction "VCCA_1") (pintype "bidirectional"))
      (node (ref "LS3") (pin "2") (pinfunction "DIR_2") (pintype "bidirectional"))
      (node (ref "LS4") (pin "1") (pinfunction "VCCA_1") (pintype "bidirectional"))
      (node (ref "LS4") (pin "2") (pinfunction "DIR_2") (pintype "bidirectional"))
      (node (ref "LS5") (pin "1") (pinfunction "VCCA_1") (pintype "power_in"))
      (node (ref "LS6") (pin "1") (pinfunction "VCCA_1") (pintype "power_in"))
      (node (ref "LS6") (pin "5") (pinfunction "DIR_5") (pintype "input"))
      (node (ref "MEM") (pin "6") (pinfunction "ORG_6") (pintype "bidirectional"))
      (node (ref "MEM") (pin "8") (pinfunction "VCC_8") (pintype "bidirectional"))
      (node (ref "PROG") (pin "2") (pinfunction "2_2") (pintype "passive"))
      (node (ref "R1") (pin "2") (pinfunction "2_2") (pintype "passive"))
      (node (ref "R10") (pin "2") (pinfunction "2_2") (pintype "passive"))
      (node (ref "R11") (pin "2") (pinfunction "2_2") (pintype "passive"))
      (node (ref "R12") (pin "2") (pinfunction "2_2") (pintype "passive"))
      (node (ref "R2") (pin "2") (pinfunction "2_2") (pintype "passive"))
      (node (ref "R3") (pin "2") (pinfunction "2_2") (pintype "passive"))
      (node (ref "R4") (pin "2") (pinfunction "2_2") (pintype "passive"))
      (node (ref "R7") (pin "2") (pinfunction "2_2") (pintype "passive"))
      (node (ref "R9") (pin "1") (pinfunction "1_1") (pintype "passive"))
      (node (ref "VC") (pin "2") (pinfunction "VOUT_2") (pintype "bidirectional"))
    )
    (net (code "42") (name "3.3V_CPUBRD") (class "Default")
      (node (ref "JP10") (pin "3") (pinfunction "3_3") (pintype "passive"))
      (node (ref "JP11") (pin "3") (pinfunction "3_3") (pintype "passive"))
      (node (ref "JP8") (pin "2") (pinfunction "2_2") (pintype "passive"))
    )
    (net (code "43") (name "5V_CPUBRD") (class "Default")
      (node (ref "JP10") (pin "2") (pinfunction "2_2") (pintype "passive"))
      (node (ref "JP11") (pin "2") (pinfunction "2_2") (pintype "passive"))
      (node (ref "JP7") (pin "2") (pinfunction "2_2") (pintype "passive"))
    )
    (net (code "44") (name "GND") (class "Default")
      (node (ref "1.8V_LED") (pin "C") (pinfunction "C_C") (pintype "passive"))
      (node (ref "3.3V_LED") (pin "C") (pinfunction "C_C") (pintype "passive"))
      (node (ref "5V_LED") (pin "C") (pinfunction "C_C") (pintype "passive"))
      (node (ref "C1") (pin "1") (pinfunction "1_1") (pintype "passive"))
      (node (ref "C10") (pin "1") (pinfunction "1_1") (pintype "passive"))
      (node (ref "C11") (pin "-") (pinfunction "-_-") (pintype "passive"))
      (node (ref "C12") (pin "1") (pinfunction "1_1") (pintype "passive"))
      (node (ref "C13") (pin "1") (pinfunction "1_1") (pintype "passive"))
      (node (ref "C14") (pin "-") (pinfunction "-_-") (pintype "passive"))
      (node (ref "C15") (pin "1") (pinfunction "1_1") (pintype "passive"))
      (node (ref "C16") (pin "1") (pinfunction "1_1") (pintype "passive"))
      (node (ref "C17") (pin "1") (pinfunction "1_1") (pintype "passive"))
      (node (ref "C18") (pin "1") (pinfunction "1_1") (pintype "passive"))
      (node (ref "C19") (pin "1") (pinfunction "1_1") (pintype "passive"))
      (node (ref "C2") (pin "1") (pinfunction "1_1") (pintype "passive"))
      (node (ref "C20") (pin "1") (pinfunction "1_1") (pintype "passive"))
      (node (ref "C21") (pin "2") (pinfunction "2_2") (pintype "passive"))
      (node (ref "C22") (pin "2") (pinfunction "2_2") (pintype "passive"))
      (node (ref "C23") (pin "1") (pinfunction "1_1") (pintype "passive"))
      (node (ref "C24") (pin "1") (pinfunction "1_1") (pintype "passive"))
      (node (ref "C25") (pin "2") (pinfunction "2_2") (pintype "passive"))
      (node (ref "C26") (pin "2") (pinfunction "2_2") (pintype "passive"))
      (node (ref "C27") (pin "-") (pinfunction "-_-") (pintype "passive"))
      (node (ref "C28") (pin "-") (pinfunction "-_-") (pintype "passive"))
      (node (ref "C29") (pin "-") (pinfunction "-_-") (pintype "passive"))
      (node (ref "C3") (pin "1") (pinfunction "1_1") (pintype "passive"))
      (node (ref "C30") (pin "-") (pinfunction "-_-") (pintype "passive"))
      (node (ref "C4") (pin "1") (pinfunction "1_1") (pintype "passive"))
      (node (ref "C5") (pin "1") (pinfunction "1_1") (pintype "passive"))
      (node (ref "C6") (pin "1") (pinfunction "1_1") (pintype "passive"))
      (node (ref "C7") (pin "1") (pinfunction "1_1") (pintype "passive"))
      (node (ref "C8") (pin "-") (pinfunction "-_-") (pintype "passive"))
      (node (ref "C9") (pin "-") (pinfunction "-_-") (pintype "passive"))
      (node (ref "CONN1") (pin "GND") (pinfunction "GND_GND") (pintype "bidirectional"))
      (node (ref "IC") (pin "1") (pinfunction "GND0_1") (pintype "bidirectional"))
      (node (ref "IC") (pin "10") (pinfunction "AGND_10") (pintype "bidirectional"))
      (node (ref "IC") (pin "11") (pinfunction "GND2_11") (pintype "bidirectional"))
      (node (ref "IC") (pin "13") (pinfunction "TEST_13") (pintype "bidirectional"))
      (node (ref "IC") (pin "15") (pinfunction "GND3_15") (pintype "bidirectional"))
      (node (ref "IC") (pin "25") (pinfunction "GND4_25") (pintype "bidirectional"))
      (node (ref "IC") (pin "35") (pinfunction "GND5_35") (pintype "bidirectional"))
      (node (ref "IC") (pin "47") (pinfunction "GND6_47") (pintype "bidirectional"))
      (node (ref "IC") (pin "5") (pinfunction "GND1_5") (pintype "bidirectional"))
      (node (ref "IC") (pin "51") (pinfunction "GND7_51") (pintype "bidirectional"))
      (node (ref "JP10") (pin "12") (pinfunction "12_12") (pintype "passive"))
      (node (ref "JP10") (pin "24") (pinfunction "24_24") (pintype "passive"))
      (node (ref "JP10") (pin "5") (pinfunction "5_5") (pintype "passive"))
      (node (ref "JP11") (pin "12") (pinfunction "12_12") (pintype "passive"))
      (node (ref "JP11") (pin "24") (pinfunction "24_24") (pintype "passive"))
      (node (ref "JP11") (pin "5") (pinfunction "5_5") (pintype "passive"))
      (node (ref "JP12") (pin "12") (pinfunction "12_12") (pintype "passive"))
      (node (ref "JP12") (pin "24") (pinfunction "24_24") (pintype "passive"))
      (node (ref "JP13") (pin "12") (pinfunction "12_12") (pintype "passive"))
      (node (ref "JP13") (pin "24") (pinfunction "24_24") (pintype "passive"))
      (node (ref "JTAG") (pin "10") (pinfunction "KL_10") (pintype "passive"))
      (node (ref "JTAG") (pin "12") (pinfunction "KL_12") (pintype "passive"))
      (node (ref "JTAG") (pin "14") (pinfunction "KL_14") (pintype "passive"))
      (node (ref "JTAG") (pin "16") (pinfunction "KL_16") (pintype "passive"))
      (node (ref "JTAG") (pin "18") (pinfunction "KL_18") (pintype "passive"))
      (node (ref "JTAG") (pin "20") (pinfunction "KL_20") (pintype "passive"))
      (node (ref "JTAG") (pin "4") (pinfunction "KL_4") (pintype "passive"))
      (node (ref "JTAG") (pin "6") (pinfunction "KL_6") (pintype "passive"))
      (node (ref "JTAG") (pin "8") (pinfunction "KL_8") (pintype "passive"))
      (node (ref "LS1") (pin "10") (pinfunction "A8_10") (pintype "bidirectional"))
      (node (ref "LS1") (pin "11") (pinfunction "GND_11") (pintype "bidirectional"))
      (node (ref "LS1") (pin "12") (pinfunction "GND2_12") (pintype "bidirectional"))
      (node (ref "LS1") (pin "13") (pinfunction "GND3_13") (pintype "bidirectional"))
      (node (ref "LS1") (pin "6") (pinfunction "A4_6") (pintype "bidirectional"))
      (node (ref "LS1") (pin "7") (pinfunction "A5_7") (pintype "bidirectional"))
      (node (ref "LS1") (pin "8") (pinfunction "A6_8") (pintype "bidirectional"))
      (node (ref "LS1") (pin "9") (pinfunction "A7_9") (pintype "bidirectional"))
      (node (ref "LS2") (pin "10") (pinfunction "A8_10") (pintype "bidirectional"))
      (node (ref "LS2") (pin "11") (pinfunction "GND_11") (pintype "bidirectional"))
      (node (ref "LS2") (pin "12") (pinfunction "GND2_12") (pintype "bidirectional"))
      (node (ref "LS2") (pin "13") (pinfunction "GND3_13") (pintype "bidirectional"))
      (node (ref "LS2") (pin "2") (pinfunction "DIR_2") (pintype "bidirectional"))
      (node (ref "LS2") (pin "22") (pinfunction "OE_22") (pintype "bidirectional"))
      (node (ref "LS2") (pin "6") (pinfunction "A4_6") (pintype "bidirectional"))
      (node (ref "LS2") (pin "7") (pinfunction "A5_7") (pintype "bidirectional"))
      (node (ref "LS2") (pin "8") (pinfunction "A6_8") (pintype "bidirectional"))
      (node (ref "LS2") (pin "9") (pinfunction "A7_9") (pintype "bidirectional"))
      (node (ref "LS3") (pin "10") (pinfunction "A8_10") (pintype "bidirectional"))
      (node (ref "LS3") (pin "11") (pinfunction "GND_11") (pintype "bidirectional"))
      (node (ref "LS3") (pin "12") (pinfunction "GND2_12") (pintype "bidirectional"))
      (node (ref "LS3") (pin "13") (pinfunction "GND3_13") (pintype "bidirectional"))
      (node (ref "LS3") (pin "4") (pinfunction "A2_4") (pintype "bidirectional"))
      (node (ref "LS3") (pin "5") (pinfunction "A3_5") (pintype "bidirectional"))
      (node (ref "LS3") (pin "6") (pinfunction "A4_6") (pintype "bidirectional"))
      (node (ref "LS3") (pin "7") (pinfunction "A5_7") (pintype "bidirectional"))
      (node (ref "LS3") (pin "8") (pinfunction "A6_8") (pintype "bidirectional"))
      (node (ref "LS3") (pin "9") (pinfunction "A7_9") (pintype "bidirectional"))
      (node (ref "LS4") (pin "10") (pinfunction "A8_10") (pintype "bidirectional"))
      (node (ref "LS4") (pin "11") (pinfunction "GND_11") (pintype "bidirectional"))
      (node (ref "LS4") (pin "12") (pinfunction "GND2_12") (pintype "bidirectional"))
      (node (ref "LS4") (pin "13") (pinfunction "GND3_13") (pintype "bidirectional"))
      (node (ref "LS4") (pin "4") (pinfunction "A2_4") (pintype "bidirectional"))
      (node (ref "LS4") (pin "5") (pinfunction "A3_5") (pintype "bidirectional"))
      (node (ref "LS4") (pin "6") (pinfunction "A4_6") (pintype "bidirectional"))
      (node (ref "LS4") (pin "7") (pinfunction "A5_7") (pintype "bidirectional"))
      (node (ref "LS4") (pin "8") (pinfunction "A6_8") (pintype "bidirectional"))
      (node (ref "LS4") (pin "9") (pinfunction "A7_9") (pintype "bidirectional"))
      (node (ref "LS5") (pin "4") (pinfunction "GND_4") (pintype "passive"))
      (node (ref "LS5") (pin "5") (pinfunction "DIR_5") (pintype "input"))
      (node (ref "LS6") (pin "4") (pinfunction "GND_4") (pintype "passive"))
      (node (ref "MEM") (pin "5") (pinfunction "GND_5") (pintype "bidirectional"))
      (node (ref "MEM") (pin "7") (pinfunction "DC_7") (pintype "bidirectional"))
      (node (ref "PROG") (pin "1") (pinfunction "1_1") (pintype "passive"))
      (node (ref "PWR_LED") (pin "C") (pinfunction "C_C") (pintype "passive"))
      (node (ref "Q1") (pin "1") (pinfunction "G_1") (pintype "passive"))
      (node (ref "Q2") (pin "1") (pinfunction "G_1") (pintype "passive"))
      (node (ref "Q3") (pin "2") (pinfunction "E_2") (pintype "bidirectional"))
      (node (ref "Q4") (pin "2") (pinfunction "E_2") (pintype "bidirectional"))
      (node (ref "Q5") (pin "2") (pinfunction "E_2") (pintype "bidirectional"))
      (node (ref "R14") (pin "2") (pinfunction "2_2") (pintype "passive"))
      (node (ref "R15") (pin "2") (pinfunction "2_2") (pintype "passive"))
      (node (ref "R6") (pin "1") (pinfunction "1_1") (pintype "passive"))
      (node (ref "R8") (pin "1") (pinfunction "1_1") (pintype "passive"))
      (node (ref "T1") (pin "E") (pinfunction "E_E") (pintype "passive"))
      (node (ref "TARGET_SW") (pin "3") (pinfunction "3_3") (pintype "passive"))
      (node (ref "TVS1") (pin "1") (pinfunction "1_1") (pintype "passive"))
      (node (ref "TVS2") (pin "1") (pinfunction "1_1") (pintype "passive"))
      (node (ref "U3") (pin "4") (pinfunction "GND_4") (pintype "bidirectional"))
      (node (ref "U3") (pin "PAD") (pinfunction "EP_PAD") (pintype "bidirectional"))
      (node (ref "U4") (pin "4") (pinfunction "GND_4") (pintype "bidirectional"))
      (node (ref "U4") (pin "PAD") (pinfunction "EP_PAD") (pintype "bidirectional"))
      (node (ref "USER_BTN1") (pin "1") (pintype "bidirectional"))
      (node (ref "USER_BTN1") (pin "2") (pintype "bidirectional"))
      (node (ref "USER_BTN2") (pin "1") (pintype "bidirectional"))
      (node (ref "USER_BTN2") (pin "2") (pintype "bidirectional"))
      (node (ref "USER_BTN3") (pin "1") (pintype "bidirectional"))
      (node (ref "USER_BTN3") (pin "2") (pintype "bidirectional"))
      (node (ref "VC") (pin "1") (pinfunction "GND_1") (pintype "bidirectional"))
      (node (ref "VME_GND") (pin "P$1") (pinfunction "1_P$1") (pintype "passive"))
      (node (ref "VMO_GND") (pin "P$1") (pinfunction "1_P$1") (pintype "passive"))
    )
    (net (code "45") (name "I2C_SCL") (class "Default")
      (node (ref "JP12") (pin "14") (pinfunction "14_14") (pintype "passive"))
      (node (ref "JP13") (pin "14") (pinfunction "14_14") (pintype "passive"))
    )
    (net (code "46") (name "I2C_SDA") (class "Default")
      (node (ref "JP12") (pin "13") (pinfunction "13_13") (pintype "passive"))
      (node (ref "JP13") (pin "13") (pinfunction "13_13") (pintype "passive"))
    )
    (net (code "47") (name "N$27") (class "Default")
      (node (ref "JP10") (pin "6") (pinfunction "6_6") (pintype "passive"))
      (node (ref "JP11") (pin "6") (pinfunction "6_6") (pintype "passive"))
    )
    (net (code "48") (name "N$28") (class "Default")
      (node (ref "JP10") (pin "7") (pinfunction "7_7") (pintype "passive"))
      (node (ref "JP11") (pin "7") (pinfunction "7_7") (pintype "passive"))
    )
    (net (code "49") (name "N$29") (class "Default")
      (node (ref "JP10") (pin "8") (pinfunction "8_8") (pintype "passive"))
      (node (ref "JP11") (pin "8") (pinfunction "8_8") (pintype "passive"))
    )
    (net (code "50") (name "N$30") (class "Default")
      (node (ref "JP10") (pin "9") (pinfunction "9_9") (pintype "passive"))
      (node (ref "JP11") (pin "9") (pinfunction "9_9") (pintype "passive"))
    )
    (net (code "51") (name "N$31") (class "Default")
      (node (ref "JP10") (pin "10") (pinfunction "10_10") (pintype "passive"))
      (node (ref "JP11") (pin "10") (pinfunction "10_10") (pintype "passive"))
    )
    (net (code "52") (name "N$32") (class "Default")
      (node (ref "JP10") (pin "11") (pinfunction "11_11") (pintype "passive"))
      (node (ref "JP11") (pin "11") (pinfunction "11_11") (pintype "passive"))
    )
    (net (code "53") (name "N$37") (class "Default")
      (node (ref "JP10") (pin "16") (pinfunction "16_16") (pintype "passive"))
      (node (ref "JP11") (pin "16") (pinfunction "16_16") (pintype "passive"))
    )
    (net (code "54") (name "N$38") (class "Default")
      (node (ref "JP10") (pin "17") (pinfunction "17_17") (pintype "passive"))
      (node (ref "JP11") (pin "17") (pinfunction "17_17") (pintype "passive"))
    )
    (net (code "55") (name "N$42") (class "Default")
      (node (ref "JP10") (pin "21") (pinfunction "21_21") (pintype "passive"))
      (node (ref "JP11") (pin "21") (pinfunction "21_21") (pintype "passive"))
    )
    (net (code "56") (name "N$43") (class "Default")
      (node (ref "JP10") (pin "22") (pinfunction "22_22") (pintype "passive"))
      (node (ref "JP11") (pin "22") (pinfunction "22_22") (pintype "passive"))
    )
    (net (code "57") (name "N$44") (class "Default")
      (node (ref "JP10") (pin "23") (pinfunction "23_23") (pintype "passive"))
      (node (ref "JP11") (pin "23") (pinfunction "23_23") (pintype "passive"))
    )
    (net (code "58") (name "N$56") (class "Default")
      (node (ref "JP12") (pin "5") (pinfunction "5_5") (pintype "passive"))
      (node (ref "JP13") (pin "5") (pinfunction "5_5") (pintype "passive"))
    )
    (net (code "59") (name "N$57") (class "Default")
      (node (ref "JP12") (pin "6") (pinfunction "6_6") (pintype "passive"))
      (node (ref "JP13") (pin "6") (pinfunction "6_6") (pintype "passive"))
    )
    (net (code "60") (name "N$58") (class "Default")
      (node (ref "JP12") (pin "7") (pinfunction "7_7") (pintype "passive"))
      (node (ref "JP13") (pin "7") (pinfunction "7_7") (pintype "passive"))
    )
    (net (code "61") (name "N$70") (class "Default")
      (node (ref "JP12") (pin "19") (pinfunction "19_19") (pintype "passive"))
      (node (ref "JP13") (pin "19") (pinfunction "19_19") (pintype "passive"))
    )
    (net (code "62") (name "Net-(1.8V_LED-PadA)") (class "Default")
      (node (ref "1.8V_LED") (pin "A") (pinfunction "A_A") (pintype "passive"))
      (node (ref "R18") (pin "1") (pinfunction "1_1") (pintype "passive"))
    )
    (net (code "63") (name "Net-(3.3V_LED-PadA)") (class "Default")
      (node (ref "3.3V_LED") (pin "A") (pinfunction "A_A") (pintype "passive"))
      (node (ref "R17") (pin "1") (pinfunction "1_1") (pintype "passive"))
    )
    (net (code "64") (name "Net-(5V_LED-PadA)") (class "Default")
      (node (ref "5V_LED") (pin "A") (pinfunction "A_A") (pintype "passive"))
      (node (ref "R16") (pin "1") (pinfunction "1_1") (pintype "passive"))
    )
    (net (code "65") (name "Net-(F1-2)") (class "Default")
      (node (ref "F1") (pin "P$2") (pinfunction "2_P$2") (pintype "passive"))
      (node (ref "Q1") (pin "3") (pinfunction "D_3") (pintype "passive"))
      (node (ref "TVS1") (pin "2") (pinfunction "2_2") (pintype "passive"))
    )
    (net (code "66") (name "Net-(F2-1)") (class "Default")
      (node (ref "F2") (pin "P$1") (pinfunction "1_P$1") (pintype "passive"))
      (node (ref "JP_PROTECTION") (pin "5") (pinfunction "5_5") (pintype "passive"))
    )
    (net (code "67") (name "Net-(F2-2)") (class "Default")
      (node (ref "F2") (pin "P$2") (pinfunction "2_P$2") (pintype "passive"))
      (node (ref "F3") (pin "P$2") (pinfunction "2_P$2") (pintype "passive"))
      (node (ref "F4") (pin "P$2") (pinfunction "2_P$2") (pintype "passive"))
      (node (ref "Q2") (pin "3") (pinfunction "D_3") (pintype "passive"))
      (node (ref "TVS2") (pin "2") (pinfunction "2_2") (pintype "passive"))
    )
    (net (code "68") (name "Net-(F3-1)") (class "Default")
      (node (ref "F3") (pin "P$1") (pinfunction "1_P$1") (pintype "passive"))
      (node (ref "JP_PROTECTION") (pin "3") (pinfunction "3_3") (pintype "passive"))
    )
    (net (code "69") (name "Net-(F4-1)") (class "Default")
      (node (ref "F4") (pin "P$1") (pinfunction "1_P$1") (pintype "passive"))
      (node (ref "JP_PROTECTION") (pin "1") (pinfunction "1_1") (pintype "passive"))
    )
    (net (code "70") (name "Net-(IC-OSC0)") (class "Default")
      (node (ref "C22") (pin "1") (pinfunction "1_1") (pintype "passive"))
      (node (ref "IC") (pin "3") (pinfunction "OSC0_3") (pintype "bidirectional"))
      (node (ref "X1") (pin "2") (pinfunction "X2_2") (pintype "bidirectional"))
    )
    (net (code "71") (name "Net-(IC-OSCI)") (class "Default")
      (node (ref "C21") (pin "1") (pinfunction "1_1") (pintype "passive"))
      (node (ref "IC") (pin "2") (pinfunction "OSCI_2") (pintype "bidirectional"))
      (node (ref "X1") (pin "1") (pinfunction "X1_1") (pintype "bidirectional"))
    )
    (net (code "72") (name "Net-(IC-REF)") (class "Default")
      (node (ref "IC") (pin "6") (pinfunction "REF_6") (pintype "bidirectional"))
      (node (ref "R8") (pin "2") (pinfunction "2_2") (pintype "passive"))
    )
    (net (code "73") (name "Net-(IC-RESET#)") (class "Default")
      (node (ref "IC") (pin "14") (pinfunction "RESET#_14") (pintype "bidirectional"))
      (node (ref "R9") (pin "2") (pinfunction "2_2") (pintype "passive"))
    )
    (net (code "74") (name "Net-(IC-VPHY)") (class "Default")
      (node (ref "C11") (pin "+") (pinfunction "+_+") (pintype "passive"))
      (node (ref "C12") (pin "2") (pinfunction "2_2") (pintype "passive"))
      (node (ref "IC") (pin "4") (pinfunction "VPHY_4") (pintype "bidirectional"))
      (node (ref "L2") (pin "1") (pinfunction "1_1") (pintype "passive"))
    )
    (net (code "75") (name "Net-(IC-VPLL)") (class "Default")
      (node (ref "C10") (pin "2") (pinfunction "2_2") (pintype "passive"))
      (node (ref "C9") (pin "+") (pinfunction "+_+") (pintype "passive"))
      (node (ref "IC") (pin "9") (pinfunction "VPLL_9") (pintype "bidirectional"))
      (node (ref "L1") (pin "1") (pinfunction "1_1") (pintype "passive"))
    )
    (net (code "76") (name "Net-(JP12-Pad8)") (class "Default")
      (node (ref "JP12") (pin "8") (pinfunction "8_8") (pintype "passive"))
      (node (ref "JP13") (pin "8") (pinfunction "8_8") (pintype "passive"))
      (node (ref "JTAG_SW") (pin "8") (pinfunction "8_8") (pintype "passive"))
    )
    (net (code "77") (name "Net-(JP12-Pad9)") (class "Default")
      (node (ref "JP12") (pin "9") (pinfunction "9_9") (pintype "passive"))
      (node (ref "JP13") (pin "9") (pinfunction "9_9") (pintype "passive"))
      (node (ref "JTAG_SW") (pin "7") (pinfunction "7_7") (pintype "passive"))
    )
    (net (code "78") (name "Net-(JP12-Pad10)") (class "Default")
      (node (ref "JP12") (pin "10") (pinfunction "10_10") (pintype "passive"))
      (node (ref "JP13") (pin "10") (pinfunction "10_10") (pintype "passive"))
      (node (ref "JTAG_SW") (pin "6") (pinfunction "6_6") (pintype "passive"))
    )
    (net (code "79") (name "Net-(JP12-Pad11)") (class "Default")
      (node (ref "JP12") (pin "11") (pinfunction "11_11") (pintype "passive"))
      (node (ref "JP13") (pin "11") (pinfunction "11_11") (pintype "passive"))
      (node (ref "JTAG_SW") (pin "5") (pinfunction "5_5") (pintype "passive"))
    )
    (net (code "80") (name "Net-(JP12-Pad15)") (class "Default")
      (node (ref "JP12") (pin "15") (pinfunction "15_15") (pintype "passive"))
      (node (ref "JP13") (pin "15") (pinfunction "15_15") (pintype "passive"))
      (node (ref "UART1_SW") (pin "8") (pinfunction "8_8") (pintype "passive"))
    )
    (net (code "81") (name "Net-(JP12-Pad16)") (class "Default")
      (node (ref "JP12") (pin "16") (pinfunction "16_16") (pintype "passive"))
      (node (ref "JP13") (pin "16") (pinfunction "16_16") (pintype "passive"))
      (node (ref "UART1_SW") (pin "7") (pinfunction "7_7") (pintype "passive"))
    )
    (net (code "82") (name "Net-(JP12-Pad17)") (class "Default")
      (node (ref "JP12") (pin "17") (pinfunction "17_17") (pintype "passive"))
      (node (ref "JP13") (pin "17") (pinfunction "17_17") (pintype "passive"))
      (node (ref "UART1_SW") (pin "6") (pinfunction "6_6") (pintype "passive"))
    )
    (net (code "83") (name "Net-(JP12-Pad18)") (class "Default")
      (node (ref "JP12") (pin "18") (pinfunction "18_18") (pintype "passive"))
      (node (ref "JP13") (pin "18") (pinfunction "18_18") (pintype "passive"))
      (node (ref "UART1_SW") (pin "5") (pinfunction "5_5") (pintype "passive"))
    )
    (net (code "84") (name "Net-(JP_MEASURE-Pad3)") (class "Default")
      (node (ref "JP_MEASURE") (pin "3") (pinfunction "3_3") (pintype "passive"))
      (node (ref "RSH") (pin "2") (pinfunction "2_2") (pintype "passive"))
    )
    (net (code "85") (name "Net-(PWR_LED-PadA)") (class "Default")
      (node (ref "PWR_LED") (pin "A") (pinfunction "A_A") (pintype "passive"))
      (node (ref "R7") (pin "1") (pinfunction "1_1") (pintype "passive"))
    )
    (net (code "86") (name "Net-(Q3-B)") (class "Default")
      (node (ref "LED_SW") (pin "6") (pinfunction "6_6") (pintype "passive"))
      (node (ref "Q3") (pin "1") (pinfunction "B_1") (pintype "bidirectional"))
    )
    (net (code "87") (name "Net-(Q3-C)") (class "Default")
      (node (ref "Q3") (pin "3") (pinfunction "C_3") (pintype "bidirectional"))
      (node (ref "R21") (pin "1") (pinfunction "1_1") (pintype "passive"))
    )
    (net (code "88") (name "Net-(Q4-B)") (class "Default")
      (node (ref "LED_SW") (pin "5") (pinfunction "5_5") (pintype "passive"))
      (node (ref "Q4") (pin "1") (pinfunction "B_1") (pintype "bidirectional"))
    )
    (net (code "89") (name "Net-(Q4-C)") (class "Default")
      (node (ref "Q4") (pin "3") (pinfunction "C_3") (pintype "bidirectional"))
      (node (ref "R22") (pin "1") (pinfunction "1_1") (pintype "passive"))
    )
    (net (code "90") (name "Net-(Q5-B)") (class "Default")
      (node (ref "LED_SW") (pin "4") (pinfunction "4_4") (pintype "passive"))
      (node (ref "Q5") (pin "1") (pinfunction "B_1") (pintype "bidirectional"))
    )
    (net (code "91") (name "Net-(Q5-C)") (class "Default")
      (node (ref "Q5") (pin "3") (pinfunction "C_3") (pintype "bidirectional"))
      (node (ref "R23") (pin "1") (pinfunction "1_1") (pintype "passive"))
    )
    (net (code "92") (name "Net-(R2-Pad1)") (class "Default")
      (node (ref "R2") (pin "1") (pinfunction "1_1") (pintype "passive"))
      (node (ref "TARGET_PRESENT") (pin "A") (pinfunction "A_A") (pintype "passive"))
    )
    (net (code "93") (name "Net-(R3-Pad1)") (class "Default")
      (node (ref "R3") (pin "1") (pinfunction "1_1") (pintype "passive"))
      (node (ref "TX") (pin "A") (pinfunction "A_A") (pintype "passive"))
    )
    (net (code "94") (name "Net-(R4-Pad1)") (class "Default")
      (node (ref "R4") (pin "1") (pinfunction "1_1") (pintype "passive"))
      (node (ref "RX") (pin "A") (pinfunction "A_A") (pintype "passive"))
    )
    (net (code "95") (name "Net-(R5-Pad1)") (class "Default")
      (node (ref "R5") (pin "1") (pinfunction "1_1") (pintype "passive"))
      (node (ref "R6") (pin "2") (pinfunction "2_2") (pintype "passive"))
      (node (ref "T1") (pin "B") (pinfunction "B_B") (pintype "passive"))
    )
    (net (code "96") (name "Net-(R21-Pad2)") (class "Default")
      (node (ref "R21") (pin "2") (pinfunction "2_2") (pintype "passive"))
      (node (ref "USER_LED3") (pin "C") (pinfunction "C_C") (pintype "passive"))
    )
    (net (code "97") (name "Net-(R22-Pad2)") (class "Default")
      (node (ref "R22") (pin "2") (pinfunction "2_2") (pintype "passive"))
      (node (ref "USER_LED2") (pin "C") (pinfunction "C_C") (pintype "passive"))
    )
    (net (code "98") (name "Net-(R23-Pad2)") (class "Default")
      (node (ref "R23") (pin "2") (pinfunction "2_2") (pintype "passive"))
      (node (ref "USER_LED1") (pin "C") (pinfunction "C_C") (pintype "passive"))
    )
    (net (code "99") (name "Net-(U3-NR)") (class "Default")
      (node (ref "C25") (pin "1") (pinfunction "1_1") (pintype "passive"))
      (node (ref "U3") (pin "7") (pinfunction "NR_7") (pintype "bidirectional"))
    )
    (net (code "100") (name "Net-(U3-SENSE{slash}ADJ)") (class "Default")
      (node (ref "R14") (pin "1") (pinfunction "1_1") (pintype "passive"))
      (node (ref "R19") (pin "2") (pinfunction "2_2") (pintype "passive"))
      (node (ref "U3") (pin "3") (pinfunction "SENSE/ADJ_3") (pintype "bidirectional"))
    )
    (net (code "101") (name "Net-(U4-NR)") (class "Default")
      (node (ref "C26") (pin "1") (pinfunction "1_1") (pintype "passive"))
      (node (ref "U4") (pin "7") (pinfunction "NR_7") (pintype "bidirectional"))
    )
    (net (code "102") (name "Net-(U4-SENSE{slash}ADJ)") (class "Default")
      (node (ref "R15") (pin "1") (pinfunction "1_1") (pintype "passive"))
      (node (ref "R20") (pin "2") (pinfunction "2_2") (pintype "passive"))
      (node (ref "U4") (pin "3") (pinfunction "SENSE/ADJ_3") (pintype "bidirectional"))
    )
    (net (code "103") (name "Net-(VA_IN-1)") (class "Default")
      (node (ref "JP_MEASURE") (pin "1") (pinfunction "1_1") (pintype "passive"))
      (node (ref "RSH") (pin "1") (pinfunction "1_1") (pintype "passive"))
      (node (ref "VA_IN") (pin "P$1") (pinfunction "1_P$1") (pintype "passive"))
      (node (ref "VME_IN") (pin "P$1") (pinfunction "1_P$1") (pintype "passive"))
    )
    (net (code "104") (name "Net-(VA_OUT-1)") (class "Default")
      (node (ref "JP_MEASURE") (pin "2") (pinfunction "2_2") (pintype "passive"))
      (node (ref "JP_PROTECTION") (pin "2") (pinfunction "2_2") (pintype "passive"))
      (node (ref "JP_PROTECTION") (pin "4") (pinfunction "4_4") (pintype "passive"))
      (node (ref "JP_PROTECTION") (pin "6") (pinfunction "6_6") (pintype "passive"))
      (node (ref "JP_PROTECTION") (pin "8") (pinfunction "8_8") (pintype "passive"))
      (node (ref "VA_OUT") (pin "P$1") (pinfunction "1_P$1") (pintype "passive"))
    )
    (net (code "105") (name "Net-(VC-VIN)") (class "Default")
      (node (ref "C15") (pin "2") (pinfunction "2_2") (pintype "passive"))
      (node (ref "CONN1") (pin "VUSB") (pinfunction "VUSB_VUSB") (pintype "bidirectional"))
      (node (ref "VC") (pin "3") (pinfunction "VIN_3") (pintype "bidirectional"))
    )
    (net (code "106") (name "SPI_SCK") (class "Default")
      (node (ref "JP12") (pin "3") (pinfunction "3_3") (pintype "passive"))
      (node (ref "JP13") (pin "3") (pinfunction "3_3") (pintype "passive"))
    )
    (net (code "107") (name "SPI_SDI") (class "Default")
      (node (ref "JP12") (pin "1") (pinfunction "1_1") (pintype "passive"))
      (node (ref "JP13") (pin "1") (pinfunction "1_1") (pintype "passive"))
    )
    (net (code "108") (name "SPI_SDO") (class "Default")
      (node (ref "JP12") (pin "2") (pinfunction "2_2") (pintype "passive"))
      (node (ref "JP13") (pin "2") (pinfunction "2_2") (pintype "passive"))
    )
    (net (code "109") (name "TCK-1") (class "Default")
      (node (ref "JTAG") (pin "9") (pinfunction "KL_9") (pintype "passive"))
      (node (ref "JTAG_SW") (pin "4") (pinfunction "4_4") (pintype "passive"))
      (node (ref "LS1") (pin "19") (pinfunction "B3_19") (pintype "bidirectional"))
    )
    (net (code "110") (name "TDI-1") (class "Default")
      (node (ref "JTAG") (pin "5") (pinfunction "KL_5") (pintype "passive"))
      (node (ref "JTAG_SW") (pin "3") (pinfunction "3_3") (pintype "passive"))
      (node (ref "LS1") (pin "21") (pinfunction "B1_21") (pintype "bidirectional"))
    )
    (net (code "111") (name "TDO{slash}DI-1") (class "Default")
      (node (ref "JTAG") (pin "13") (pinfunction "KL_13") (pintype "passive"))
      (node (ref "JTAG_SW") (pin "2") (pinfunction "2_2") (pintype "passive"))
      (node (ref "LS2") (pin "21") (pinfunction "B1_21") (pintype "bidirectional"))
    )
    (net (code "112") (name "TMS-1") (class "Default")
      (node (ref "JTAG") (pin "7") (pinfunction "KL_7") (pintype "passive"))
      (node (ref "JTAG_SW") (pin "1") (pinfunction "1_1") (pintype "passive"))
      (node (ref "LS1") (pin "20") (pinfunction "B2_20") (pintype "bidirectional"))
    )
    (net (code "113") (name "UART1_RX") (class "Default")
      (node (ref "LS6") (pin "7") (pinfunction "B1_7") (pintype "bidirectional"))
      (node (ref "UART1_SW") (pin "1") (pinfunction "1_1") (pintype "passive"))
    )
    (net (code "114") (name "UART1_TX") (class "Default")
      (node (ref "LS5") (pin "7") (pinfunction "B1_7") (pintype "bidirectional"))
      (node (ref "UART1_SW") (pin "2") (pinfunction "2_2") (pintype "passive"))
    )
    (net (code "115") (name "UART2_RX") (class "Default")
      (node (ref "JP12") (pin "20") (pinfunction "20_20") (pintype "passive"))
      (node (ref "JP13") (pin "20") (pinfunction "20_20") (pintype "passive"))
    )
    (net (code "116") (name "UART2_TX") (class "Default")
      (node (ref "JP12") (pin "21") (pinfunction "21_21") (pintype "passive"))
      (node (ref "JP13") (pin "21") (pinfunction "21_21") (pintype "passive"))
    )
    (net (code "117") (name "USER_BTN1") (class "Default")
      (node (ref "JP10") (pin "18") (pinfunction "18_18") (pintype "passive"))
      (node (ref "JP11") (pin "18") (pinfunction "18_18") (pintype "passive"))
      (node (ref "USER_BTN1") (pin "3") (pintype "bidirectional"))
      (node (ref "USER_BTN1") (pin "4") (pintype "bidirectional"))
    )
    (net (code "118") (name "USER_BTN2") (class "Default")
      (node (ref "JP10") (pin "19") (pinfunction "19_19") (pintype "passive"))
      (node (ref "JP11") (pin "19") (pinfunction "19_19") (pintype "passive"))
      (node (ref "USER_BTN2") (pin "3") (pintype "bidirectional"))
      (node (ref "USER_BTN2") (pin "4") (pintype "bidirectional"))
    )
    (net (code "119") (name "USER_BTN3") (class "Default")
      (node (ref "JP10") (pin "20") (pinfunction "20_20") (pintype "passive"))
      (node (ref "JP11") (pin "20") (pinfunction "20_20") (pintype "passive"))
      (node (ref "USER_BTN3") (pin "3") (pintype "bidirectional"))
      (node (ref "USER_BTN3") (pin "4") (pintype "bidirectional"))
    )
    (net (code "120") (name "USER_LED1") (class "Default")
      (node (ref "JP10") (pin "13") (pinfunction "13_13") (pintype "passive"))
      (node (ref "JP11") (pin "13") (pinfunction "13_13") (pintype "passive"))
      (node (ref "LED_SW") (pin "3") (pinfunction "3_3") (pintype "passive"))
    )
    (net (code "121") (name "USER_LED2") (class "Default")
      (node (ref "JP10") (pin "14") (pinfunction "14_14") (pintype "passive"))
      (node (ref "JP11") (pin "14") (pinfunction "14_14") (pintype "passive"))
      (node (ref "LED_SW") (pin "2") (pinfunction "2_2") (pintype "passive"))
    )
    (net (code "122") (name "USER_LED3") (class "Default")
      (node (ref "JP10") (pin "15") (pinfunction "15_15") (pintype "passive"))
      (node (ref "JP11") (pin "15") (pinfunction "15_15") (pintype "passive"))
      (node (ref "LED_SW") (pin "1") (pinfunction "1_1") (pintype "passive"))
    )
    (net (code "123") (name "V_CPU") (class "Default")
      (node (ref "JP10") (pin "1") (pinfunction "1_1") (pintype "passive"))
      (node (ref "JP11") (pin "1") (pinfunction "1_1") (pintype "passive"))
      (node (ref "TARGET_SW") (pin "1") (pinfunction "1_1") (pintype "passive"))
    )
    (net (code "124") (name "unconnected-(CONN1B-USBID-PadID)") (class "Default")
      (node (ref "CONN1") (pin "ID") (pinfunction "USBID_ID") (pintype "bidirectional"))
    )
    (net (code "125") (name "unconnected-(IC-ACBUS4{slash}TXLED#{slash}GPIOH4-Pad30)") (class "Default")
      (node (ref "IC") (pin "30") (pinfunction "ACBUS4/TXLED#/GPIOH4_30") (pintype "bidirectional"))
    )
    (net (code "126") (name "unconnected-(IC-ACBUS5{slash}GPIOH5-Pad32)") (class "Default")
      (node (ref "IC") (pin "32") (pinfunction "ACBUS5/GPIOH5_32") (pintype "bidirectional"))
    )
    (net (code "127") (name "unconnected-(IC-ACBUS6{slash}GPIOH6-Pad33)") (class "Default")
      (node (ref "IC") (pin "33") (pinfunction "ACBUS6/GPIOH6_33") (pintype "bidirectional"))
    )
    (net (code "128") (name "unconnected-(IC-ACBUS7{slash}GPIOH7-Pad34)") (class "Default")
      (node (ref "IC") (pin "34") (pinfunction "ACBUS7/GPIOH7_34") (pintype "bidirectional"))
    )
    (net (code "129") (name "unconnected-(IC-BCBUS0{slash}GPIOH1-Pad48)") (class "Default")
      (node (ref "IC") (pin "48") (pinfunction "BCBUS0/GPIOH1_48") (pintype "bidirectional"))
    )
    (net (code "130") (name "unconnected-(IC-BCBUS1{slash}GPIOH2-Pad52)") (class "Default")
      (node (ref "IC") (pin "52") (pinfunction "BCBUS1/GPIOH2_52") (pintype "bidirectional"))
    )
    (net (code "131") (name "unconnected-(IC-BCBUS2-Pad53)") (class "Default")
      (node (ref "IC") (pin "53") (pinfunction "BCBUS2_53") (pintype "bidirectional"))
    )
    (net (code "132") (name "unconnected-(IC-BCBUS5{slash}GPIOH5-Pad57)") (class "Default")
      (node (ref "IC") (pin "57") (pinfunction "BCBUS5/GPIOH5_57") (pintype "bidirectional"))
    )
    (net (code "133") (name "unconnected-(IC-BCBUS6{slash}GPIOH6-Pad58)") (class "Default")
      (node (ref "IC") (pin "58") (pinfunction "BCBUS6/GPIOH6_58") (pintype "bidirectional"))
    )
    (net (code "134") (name "unconnected-(IC-BCBUS7{slash}GPIOH7-Pad59)") (class "Default")
      (node (ref "IC") (pin "59") (pinfunction "BCBUS7/GPIOH7_59") (pintype "bidirectional"))
    )
    (net (code "135") (name "unconnected-(IC-BDBUS4{slash}DTR#{slash}GPIOL0-Pad43)") (class "Default")
      (node (ref "IC") (pin "43") (pinfunction "BDBUS4/DTR#/GPIOL0_43") (pintype "bidirectional"))
    )
    (net (code "136") (name "unconnected-(IC-BDBUS5{slash}DSR#{slash}GPIOL1-Pad44)") (class "Default")
      (node (ref "IC") (pin "44") (pinfunction "BDBUS5/DSR#/GPIOL1_44") (pintype "bidirectional"))
    )
    (net (code "137") (name "unconnected-(IC-BDBUS6{slash}DCD#{slash}GPIOL2-Pad45)") (class "Default")
      (node (ref "IC") (pin "45") (pinfunction "BDBUS6/DCD#/GPIOL2_45") (pintype "bidirectional"))
    )
    (net (code "138") (name "unconnected-(IC-BDBUS7{slash}RI#{slash}GPIOL3-Pad46)") (class "Default")
      (node (ref "IC") (pin "46") (pinfunction "BDBUS7/RI#/GPIOL3_46") (pintype "bidirectional"))
    )
    (net (code "139") (name "unconnected-(IC-PWREN#-Pad60)") (class "Default")
      (node (ref "IC") (pin "60") (pinfunction "PWREN#_60") (pintype "bidirectional"))
    )
    (net (code "140") (name "unconnected-(IC-SUSPEND#-Pad36)") (class "Default")
      (node (ref "IC") (pin "36") (pinfunction "SUSPEND#_36") (pintype "bidirectional"))
    )
    (net (code "141") (name "unconnected-(JTAGI-KL-Pad17)") (class "Default")
      (node (ref "JTAG") (pin "17") (pinfunction "KL_17") (pintype "passive"))
    )
    (net (code "142") (name "unconnected-(JTAGK-KL-Pad19)") (class "Default")
      (node (ref "JTAG") (pin "19") (pinfunction "KL_19") (pintype "passive"))
    )
    (net (code "143") (name "unconnected-(LS1-B4-Pad18)") (class "Default")
      (node (ref "LS1") (pin "18") (pinfunction "B4_18") (pintype "bidirectional"))
    )
    (net (code "144") (name "unconnected-(LS1-B5-Pad17)") (class "Default")
      (node (ref "LS1") (pin "17") (pinfunction "B5_17") (pintype "bidirectional"))
    )
    (net (code "145") (name "unconnected-(LS1-B6-Pad16)") (class "Default")
      (node (ref "LS1") (pin "16") (pinfunction "B6_16") (pintype "bidirectional"))
    )
    (net (code "146") (name "unconnected-(LS1-B7-Pad15)") (class "Default")
      (node (ref "LS1") (pin "15") (pinfunction "B7_15") (pintype "bidirectional"))
    )
    (net (code "147") (name "unconnected-(LS1-B8-Pad14)") (class "Default")
      (node (ref "LS1") (pin "14") (pinfunction "B8_14") (pintype "bidirectional"))
    )
    (net (code "148") (name "unconnected-(LS2-B4-Pad18)") (class "Default")
      (node (ref "LS2") (pin "18") (pinfunction "B4_18") (pintype "bidirectional"))
    )
    (net (code "149") (name "unconnected-(LS2-B5-Pad17)") (class "Default")
      (node (ref "LS2") (pin "17") (pinfunction "B5_17") (pintype "bidirectional"))
    )
    (net (code "150") (name "unconnected-(LS2-B6-Pad16)") (class "Default")
      (node (ref "LS2") (pin "16") (pinfunction "B6_16") (pintype "bidirectional"))
    )
    (net (code "151") (name "unconnected-(LS2-B7-Pad15)") (class "Default")
      (node (ref "LS2") (pin "15") (pinfunction "B7_15") (pintype "bidirectional"))
    )
    (net (code "152") (name "unconnected-(LS2-B8-Pad14)") (class "Default")
      (node (ref "LS2") (pin "14") (pinfunction "B8_14") (pintype "bidirectional"))
    )
    (net (code "153") (name "unconnected-(LS3-B2-Pad20)") (class "Default")
      (node (ref "LS3") (pin "20") (pinfunction "B2_20") (pintype "bidirectional"))
    )
    (net (code "154") (name "unconnected-(LS3-B3-Pad19)") (class "Default")
      (node (ref "LS3") (pin "19") (pinfunction "B3_19") (pintype "bidirectional"))
    )
    (net (code "155") (name "unconnected-(LS3-B4-Pad18)") (class "Default")
      (node (ref "LS3") (pin "18") (pinfunction "B4_18") (pintype "bidirectional"))
    )
    (net (code "156") (name "unconnected-(LS3-B5-Pad17)") (class "Default")
      (node (ref "LS3") (pin "17") (pinfunction "B5_17") (pintype "bidirectional"))
    )
    (net (code "157") (name "unconnected-(LS3-B6-Pad16)") (class "Default")
      (node (ref "LS3") (pin "16") (pinfunction "B6_16") (pintype "bidirectional"))
    )
    (net (code "158") (name "unconnected-(LS3-B7-Pad15)") (class "Default")
      (node (ref "LS3") (pin "15") (pinfunction "B7_15") (pintype "bidirectional"))
    )
    (net (code "159") (name "unconnected-(LS3-B8-Pad14)") (class "Default")
      (node (ref "LS3") (pin "14") (pinfunction "B8_14") (pintype "bidirectional"))
    )
    (net (code "160") (name "unconnected-(LS4-B2-Pad20)") (class "Default")
      (node (ref "LS4") (pin "20") (pinfunction "B2_20") (pintype "bidirectional"))
    )
    (net (code "161") (name "unconnected-(LS4-B3-Pad19)") (class "Default")
      (node (ref "LS4") (pin "19") (pinfunction "B3_19") (pintype "bidirectional"))
    )
    (net (code "162") (name "unconnected-(LS4-B4-Pad18)") (class "Default")
      (node (ref "LS4") (pin "18") (pinfunction "B4_18") (pintype "bidirectional"))
    )
    (net (code "163") (name "unconnected-(LS4-B5-Pad17)") (class "Default")
      (node (ref "LS4") (pin "17") (pinfunction "B5_17") (pintype "bidirectional"))
    )
    (net (code "164") (name "unconnected-(LS4-B6-Pad16)") (class "Default")
      (node (ref "LS4") (pin "16") (pinfunction "B6_16") (pintype "bidirectional"))
    )
    (net (code "165") (name "unconnected-(LS4-B7-Pad15)") (class "Default")
      (node (ref "LS4") (pin "15") (pinfunction "B7_15") (pintype "bidirectional"))
    )
    (net (code "166") (name "unconnected-(LS4-B8-Pad14)") (class "Default")
      (node (ref "LS4") (pin "14") (pinfunction "B8_14") (pintype "bidirectional"))
    )
    (net (code "167") (name "unconnected-(U3-PWRG-Pad5)") (class "Default")
      (node (ref "U3") (pin "5") (pinfunction "PWRG_5") (pintype "bidirectional"))
    )
    (net (code "168") (name "unconnected-(U4-PWRG-Pad5)") (class "Default")
      (node (ref "U4") (pin "5") (pinfunction "PWRG_5") (pintype "bidirectional"))
    )
  )
)
